# LED_Cube_with_Rs.net
KiCad netlist of a schematic drawn in EAGLE
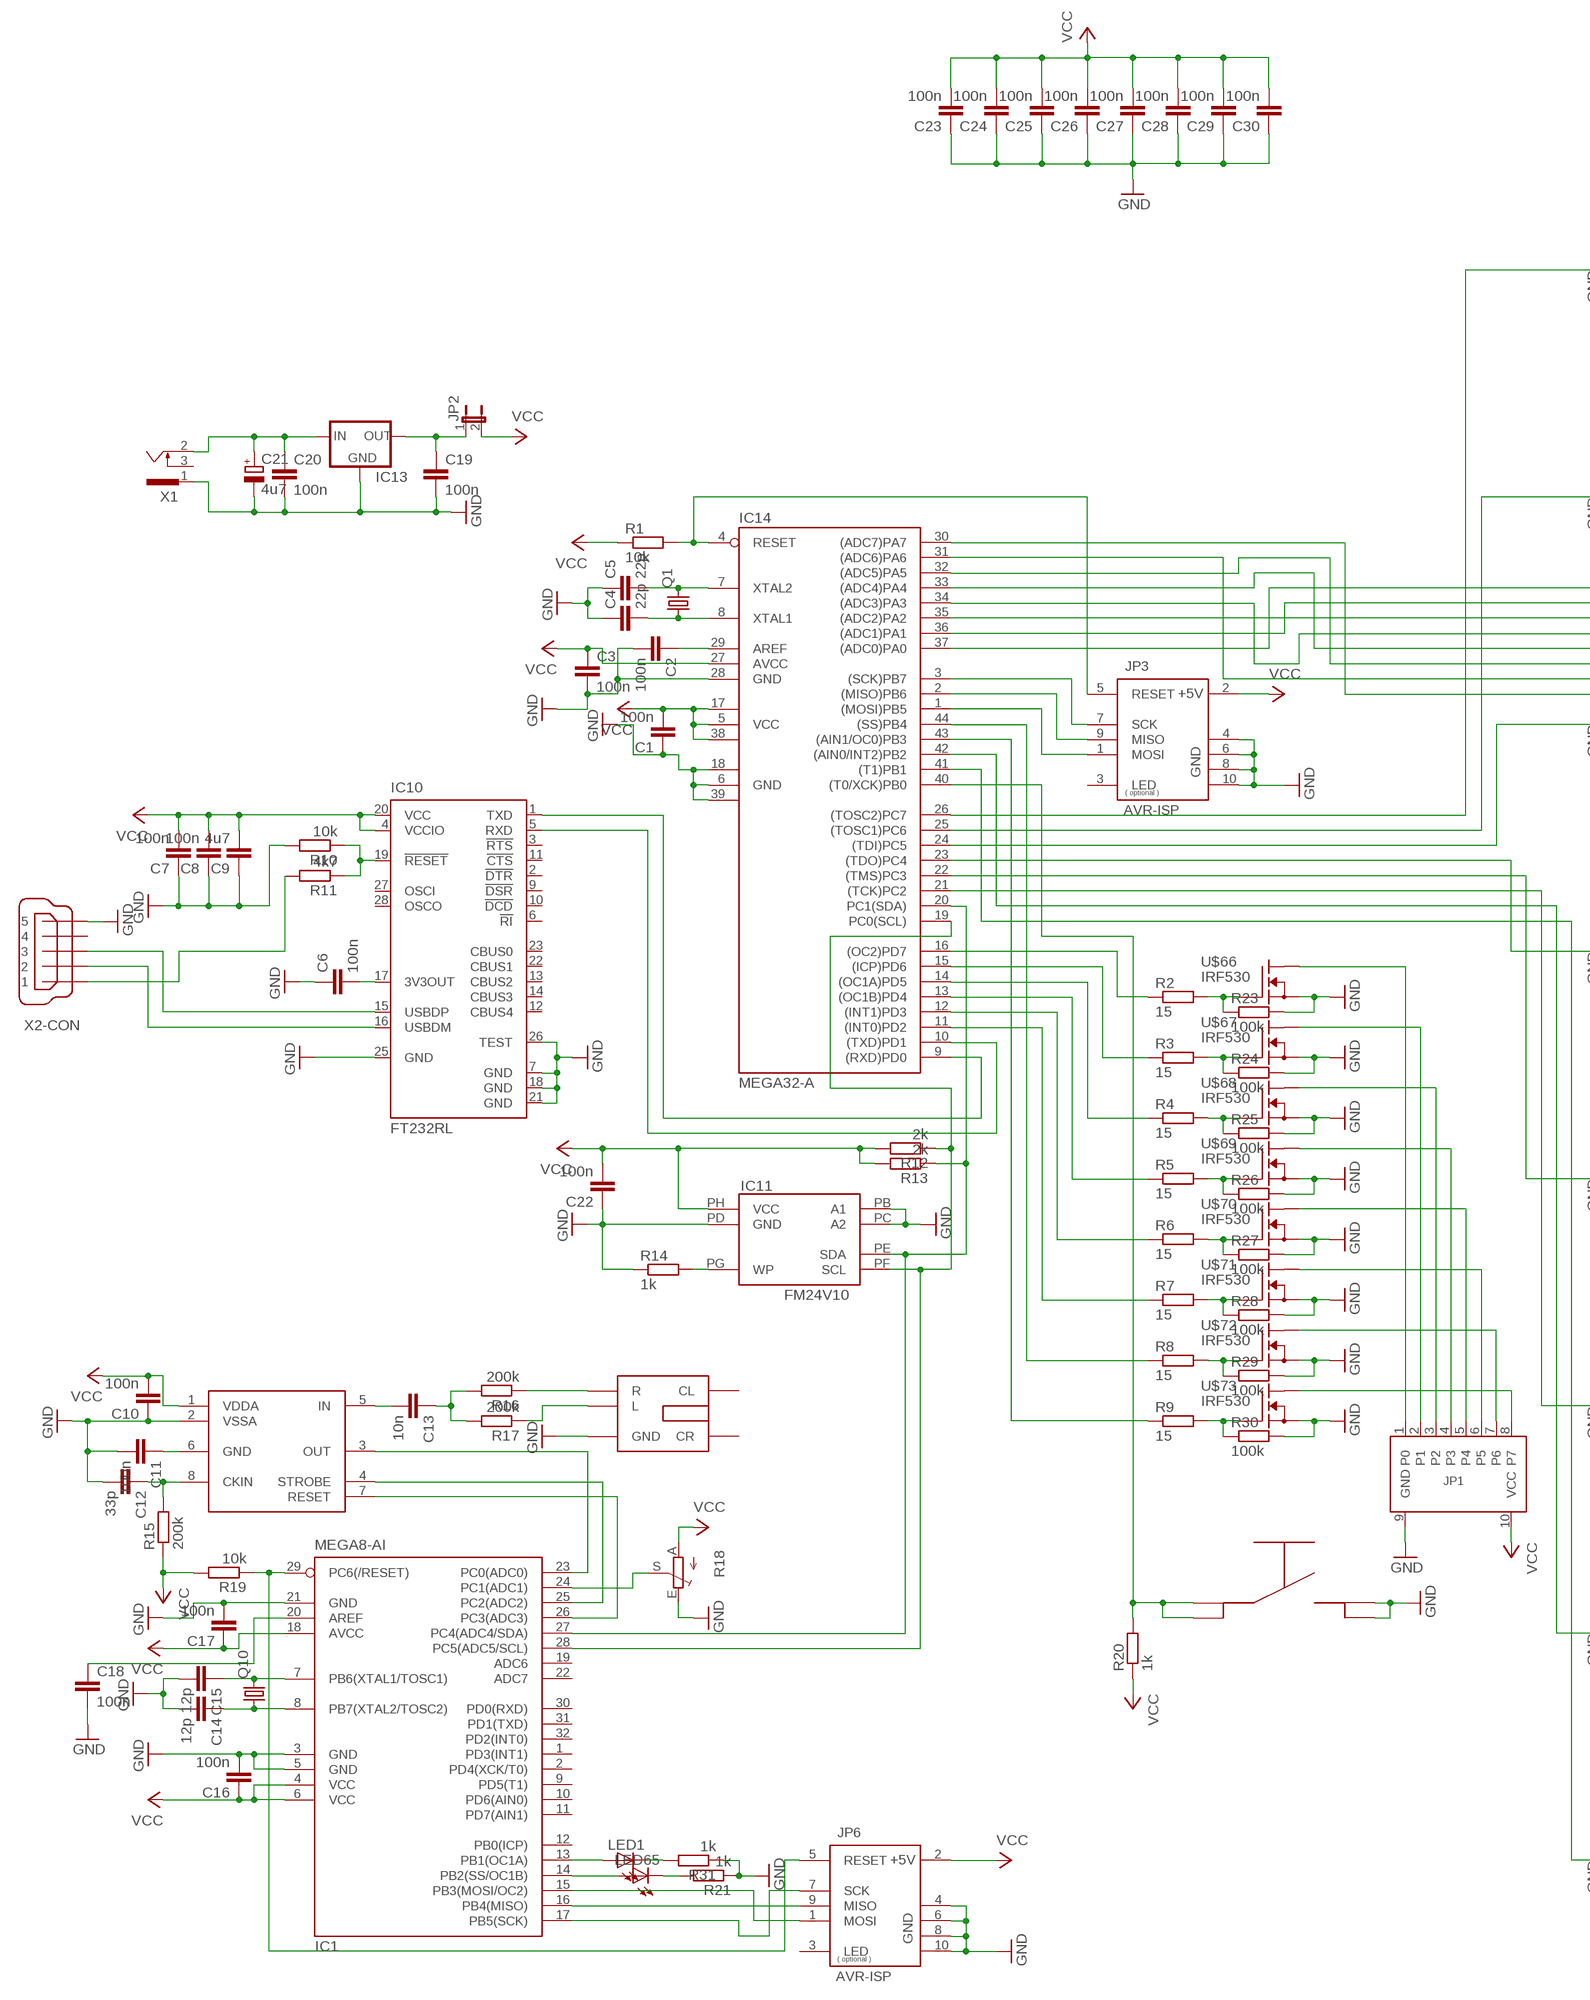
[diagram p0: schematic, sheet 1, part 1 of 2]
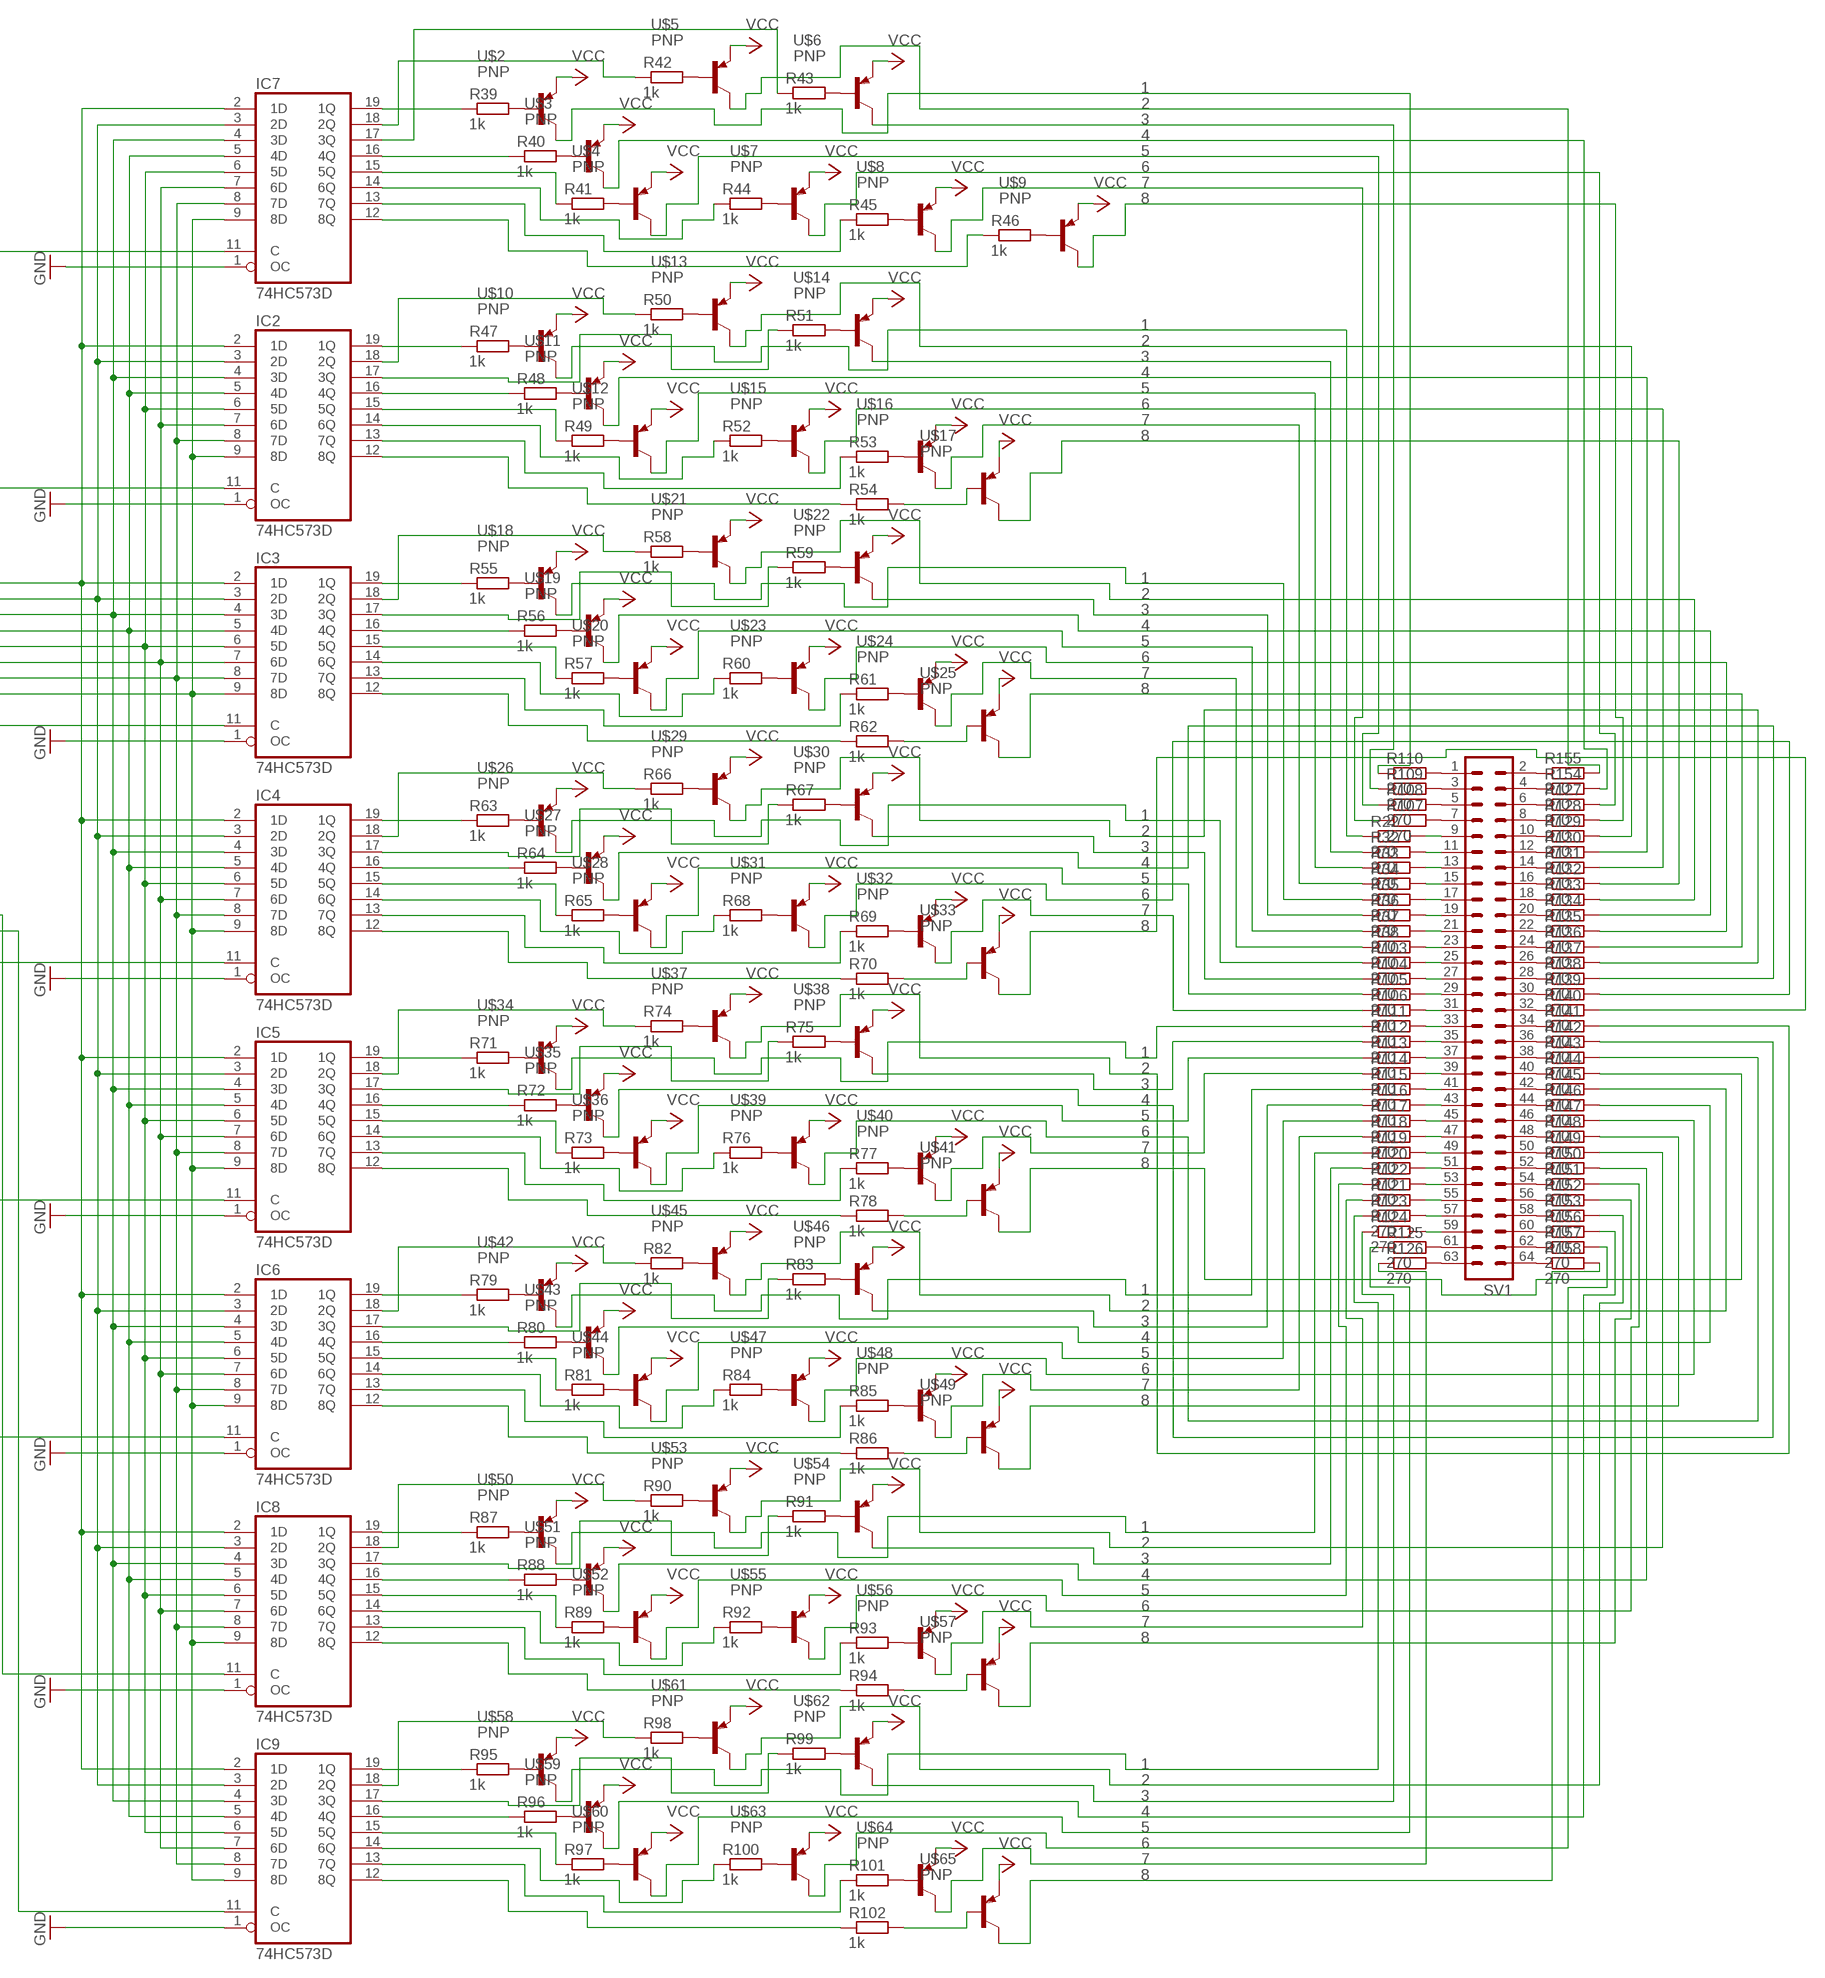
[diagram p1: schematic, sheet 1, part 2 of 2]

(export (version "E")
  (design (tool "Eeschema 10.0.6"))
  (components
    (comp (ref "C1")
      (value "100n")
      (footprint "eagle-import:C0603")
      (libsource (lib "eagle-import") (part "C-EUC0603"))
    )
    (comp (ref "C2")
      (value "100n")
      (footprint "eagle-import:C0603")
      (libsource (lib "eagle-import") (part "C-EUC0603"))
    )
    (comp (ref "C3")
      (value "100n")
      (footprint "eagle-import:C0603")
      (libsource (lib "eagle-import") (part "C-EUC0603"))
    )
    (comp (ref "C4")
      (value "22p")
      (footprint "eagle-import:C0603")
      (libsource (lib "eagle-import") (part "C-EUC0603"))
    )
    (comp (ref "C5")
      (value "22p")
      (footprint "eagle-import:C0603")
      (libsource (lib "eagle-import") (part "C-EUC0603"))
    )
    (comp (ref "C6")
      (value "100n")
      (footprint "eagle-import:C0603")
      (libsource (lib "eagle-import") (part "C-EUC0603"))
    )
    (comp (ref "C7")
      (value "100n")
      (footprint "eagle-import:C0603")
      (libsource (lib "eagle-import") (part "C-EUC0603"))
    )
    (comp (ref "C8")
      (value "100n")
      (footprint "eagle-import:C0603")
      (libsource (lib "eagle-import") (part "C-EUC0603"))
    )
    (comp (ref "C9")
      (value "4u7")
      (footprint "eagle-import:C0603")
      (libsource (lib "eagle-import") (part "C-EUC0603"))
    )
    (comp (ref "C10")
      (value "100n")
      (footprint "eagle-import:C0603")
      (libsource (lib "eagle-import") (part "C-EUC0603"))
    )
    (comp (ref "C11")
      (value "100n")
      (footprint "eagle-import:C0603")
      (libsource (lib "eagle-import") (part "C-EUC0603"))
    )
    (comp (ref "C12")
      (value "33p")
      (footprint "eagle-import:C0603")
      (libsource (lib "eagle-import") (part "C-EUC0603"))
    )
    (comp (ref "C13")
      (value "10n")
      (footprint "eagle-import:C0603")
      (libsource (lib "eagle-import") (part "C-EUC0603"))
    )
    (comp (ref "C14")
      (value "12p")
      (footprint "eagle-import:C0603")
      (libsource (lib "eagle-import") (part "C-EUC0603"))
    )
    (comp (ref "C15")
      (value "12p")
      (footprint "eagle-import:C0603")
      (libsource (lib "eagle-import") (part "C-EUC0603"))
    )
    (comp (ref "C16")
      (value "100n")
      (footprint "eagle-import:C0603")
      (libsource (lib "eagle-import") (part "C-EUC0603"))
    )
    (comp (ref "C17")
      (value "100n")
      (footprint "eagle-import:C0603")
      (libsource (lib "eagle-import") (part "C-EUC0603"))
    )
    (comp (ref "C18")
      (value "100n")
      (footprint "eagle-import:C0603")
      (libsource (lib "eagle-import") (part "C-EUC0603"))
    )
    (comp (ref "C19")
      (value "100n")
      (footprint "eagle-import:C0603")
      (libsource (lib "eagle-import") (part "C-EUC0603"))
    )
    (comp (ref "C20")
      (value "100n")
      (footprint "eagle-import:C0603")
      (libsource (lib "eagle-import") (part "C-EUC0603"))
    )
    (comp (ref "C21")
      (value "4u7")
      (footprint "eagle-import:TAP5-80")
      (libsource (lib "eagle-import") (part "CPOL-EUTAP5-80"))
    )
    (comp (ref "C22")
      (value "100n")
      (footprint "eagle-import:C0603")
      (libsource (lib "eagle-import") (part "C-EUC0603"))
    )
    (comp (ref "C23")
      (value "100n")
      (footprint "eagle-import:C0603")
      (libsource (lib "eagle-import") (part "C-EUC0603"))
    )
    (comp (ref "C24")
      (value "100n")
      (footprint "eagle-import:C0603")
      (libsource (lib "eagle-import") (part "C-EUC0603"))
    )
    (comp (ref "C25")
      (value "100n")
      (footprint "eagle-import:C0603")
      (libsource (lib "eagle-import") (part "C-EUC0603"))
    )
    (comp (ref "C26")
      (value "100n")
      (footprint "eagle-import:C0603")
      (libsource (lib "eagle-import") (part "C-EUC0603"))
    )
    (comp (ref "C27")
      (value "100n")
      (footprint "eagle-import:C0603")
      (libsource (lib "eagle-import") (part "C-EUC0603"))
    )
    (comp (ref "C28")
      (value "100n")
      (footprint "eagle-import:C0603")
      (libsource (lib "eagle-import") (part "C-EUC0603"))
    )
    (comp (ref "C29")
      (value "100n")
      (footprint "eagle-import:C0603")
      (libsource (lib "eagle-import") (part "C-EUC0603"))
    )
    (comp (ref "C30")
      (value "100n")
      (footprint "eagle-import:C0603")
      (libsource (lib "eagle-import") (part "C-EUC0603"))
    )
    (comp (ref "IC1")
      (value "MEGA8-AI")
      (footprint "eagle-import:TQFP32-08")
      (fields (field (name "MPN") "ATMEGA8-16AU"))
      (libsource (lib "eagle-import") (part "MEGA8-AI"))
    )
    (comp (ref "IC2")
      (value "74HC573D")
      (footprint "eagle-import:SO20W")
      (libsource (lib "eagle-import") (part "74573DHC"))
    )
    (comp (ref "IC3")
      (value "74HC573D")
      (footprint "eagle-import:SO20W")
      (libsource (lib "eagle-import") (part "74573DHC"))
    )
    (comp (ref "IC4")
      (value "74HC573D")
      (footprint "eagle-import:SO20W")
      (libsource (lib "eagle-import") (part "74573DHC"))
    )
    (comp (ref "IC5")
      (value "74HC573D")
      (footprint "eagle-import:SO20W")
      (libsource (lib "eagle-import") (part "74573DHC"))
    )
    (comp (ref "IC6")
      (value "74HC573D")
      (footprint "eagle-import:SO20W")
      (libsource (lib "eagle-import") (part "74573DHC"))
    )
    (comp (ref "IC7")
      (value "74HC573D")
      (footprint "eagle-import:SO20W")
      (libsource (lib "eagle-import") (part "74573DHC"))
    )
    (comp (ref "IC8")
      (value "74HC573D")
      (footprint "eagle-import:SO20W")
      (libsource (lib "eagle-import") (part "74573DHC"))
    )
    (comp (ref "IC9")
      (value "74HC573D")
      (footprint "eagle-import:SO20W")
      (libsource (lib "eagle-import") (part "74573DHC"))
    )
    (comp (ref "IC10")
      (value "FT232RL")
      (footprint "eagle-import:SSOP28")
      (libsource (lib "eagle-import") (part "FT232RL"))
    )
    (comp (ref "IC11")
      (value "FM24V10")
      (footprint "eagle-import:SOIC8")
      (libsource (lib "eagle-import") (part "FM24V10"))
    )
    (comp (ref "IC12")
      (value "MSGEQ7")
      (footprint "eagle-import:DIP8")
      (libsource (lib "eagle-import") (part "MSGEQ7"))
    )
    (comp (ref "IC13")
      (value "78XXS")
      (footprint "eagle-import:78XXS")
      (libsource (lib "eagle-import") (part "78XXS"))
    )
    (comp (ref "IC14")
      (value "MEGA32-A")
      (footprint "eagle-import:TQFP44")
      (fields (field (name "MPN") "ATMEGA32-16AU"))
      (libsource (lib "eagle-import") (part "MEGA32-A"))
    )
    (comp (ref "JP1")
      (value "PORT")
      (footprint "eagle-import:ML10")
      (libsource (lib "eagle-import") (part "PORT"))
    )
    (comp (ref "JP2")
      (value "JP1E")
      (footprint "eagle-import:JP1")
      (libsource (lib "eagle-import") (part "JP1E"))
    )
    (comp (ref "JP3")
      (value "AVR-ISP")
      (footprint "eagle-import:ML10")
      (libsource (lib "eagle-import") (part "AVR-ISP"))
    )
    (comp (ref "JP6")
      (value "AVR-ISP")
      (footprint "eagle-import:ML10")
      (libsource (lib "eagle-import") (part "AVR-ISP"))
    )
    (comp (ref "LED1")
      (value "LEDCHIPLED_0603")
      (footprint "eagle-import:CHIPLED_0603")
      (libsource (lib "eagle-import") (part "LEDCHIPLED_0603"))
    )
    (comp (ref "LED65")
      (value "LEDCHIPLED_0603")
      (footprint "eagle-import:CHIPLED_0603")
      (libsource (lib "eagle-import") (part "LEDCHIPLED_0603"))
    )
    (comp (ref "Q1")
      (value "CRYSTALHC49S")
      (footprint "eagle-import:HC49_S")
      (libsource (lib "eagle-import") (part "CRYSTALHC49S"))
    )
    (comp (ref "Q10")
      (value "CRYSTALHC49S")
      (footprint "eagle-import:HC49_S")
      (libsource (lib "eagle-import") (part "CRYSTALHC49S"))
    )
    (comp (ref "R1")
      (value "10k")
      (footprint "eagle-import:R0603")
      (libsource (lib "eagle-import") (part "R-EU_R0603"))
    )
    (comp (ref "R2")
      (value "15")
      (footprint "eagle-import:R0603")
      (libsource (lib "eagle-import") (part "R-EU_R0603"))
    )
    (comp (ref "R3")
      (value "15")
      (footprint "eagle-import:R0603")
      (libsource (lib "eagle-import") (part "R-EU_R0603"))
    )
    (comp (ref "R4")
      (value "15")
      (footprint "eagle-import:R0603")
      (libsource (lib "eagle-import") (part "R-EU_R0603"))
    )
    (comp (ref "R5")
      (value "15")
      (footprint "eagle-import:R0603")
      (libsource (lib "eagle-import") (part "R-EU_R0603"))
    )
    (comp (ref "R6")
      (value "15")
      (footprint "eagle-import:R0603")
      (libsource (lib "eagle-import") (part "R-EU_R0603"))
    )
    (comp (ref "R7")
      (value "15")
      (footprint "eagle-import:R0603")
      (libsource (lib "eagle-import") (part "R-EU_R0603"))
    )
    (comp (ref "R8")
      (value "15")
      (footprint "eagle-import:R0603")
      (libsource (lib "eagle-import") (part "R-EU_R0603"))
    )
    (comp (ref "R9")
      (value "15")
      (footprint "eagle-import:R0603")
      (libsource (lib "eagle-import") (part "R-EU_R0603"))
    )
    (comp (ref "R10")
      (value "10k")
      (footprint "eagle-import:R0603")
      (libsource (lib "eagle-import") (part "R-EU_R0603"))
    )
    (comp (ref "R11")
      (value "4k7")
      (footprint "eagle-import:R0603")
      (libsource (lib "eagle-import") (part "R-EU_R0603"))
    )
    (comp (ref "R12")
      (value "2k")
      (footprint "eagle-import:R0603")
      (libsource (lib "eagle-import") (part "R-EU_R0603"))
    )
    (comp (ref "R13")
      (value "2k")
      (footprint "eagle-import:R0603")
      (libsource (lib "eagle-import") (part "R-EU_R0603"))
    )
    (comp (ref "R14")
      (value "1k")
      (footprint "eagle-import:R0603")
      (libsource (lib "eagle-import") (part "R-EU_R0603"))
    )
    (comp (ref "R15")
      (value "200k")
      (footprint "eagle-import:R0603")
      (libsource (lib "eagle-import") (part "R-EU_R0603"))
    )
    (comp (ref "R16")
      (value "200k")
      (footprint "eagle-import:R0603")
      (libsource (lib "eagle-import") (part "R-EU_R0603"))
    )
    (comp (ref "R17")
      (value "200k")
      (footprint "eagle-import:R0603")
      (libsource (lib "eagle-import") (part "R-EU_R0603"))
    )
    (comp (ref "R18")
      (value "TRIM_EU-PT10S")
      (footprint "eagle-import:PT-10S")
      (libsource (lib "eagle-import") (part "TRIM_EU-PT10S"))
    )
    (comp (ref "R19")
      (value "10k")
      (footprint "eagle-import:R0603")
      (libsource (lib "eagle-import") (part "R-EU_R0603"))
    )
    (comp (ref "R20")
      (value "1k")
      (footprint "eagle-import:R0603")
      (libsource (lib "eagle-import") (part "R-EU_R0603"))
    )
    (comp (ref "R21")
      (value "1k")
      (footprint "eagle-import:R0603")
      (libsource (lib "eagle-import") (part "R-EU_R0603"))
    )
    (comp (ref "R22")
      (value "270")
      (footprint "eagle-import:R0603")
      (libsource (lib "eagle-import") (part "R-EU_R0603"))
    )
    (comp (ref "R23")
      (value "100k")
      (footprint "eagle-import:R0603")
      (libsource (lib "eagle-import") (part "R-EU_R0603"))
    )
    (comp (ref "R24")
      (value "100k")
      (footprint "eagle-import:R0603")
      (libsource (lib "eagle-import") (part "R-EU_R0603"))
    )
    (comp (ref "R25")
      (value "100k")
      (footprint "eagle-import:R0603")
      (libsource (lib "eagle-import") (part "R-EU_R0603"))
    )
    (comp (ref "R26")
      (value "100k")
      (footprint "eagle-import:R0603")
      (libsource (lib "eagle-import") (part "R-EU_R0603"))
    )
    (comp (ref "R27")
      (value "100k")
      (footprint "eagle-import:R0603")
      (libsource (lib "eagle-import") (part "R-EU_R0603"))
    )
    (comp (ref "R28")
      (value "100k")
      (footprint "eagle-import:R0603")
      (libsource (lib "eagle-import") (part "R-EU_R0603"))
    )
    (comp (ref "R29")
      (value "100k")
      (footprint "eagle-import:R0603")
      (libsource (lib "eagle-import") (part "R-EU_R0603"))
    )
    (comp (ref "R30")
      (value "100k")
      (footprint "eagle-import:R0603")
      (libsource (lib "eagle-import") (part "R-EU_R0603"))
    )
    (comp (ref "R31")
      (value "1k")
      (footprint "eagle-import:R0603")
      (libsource (lib "eagle-import") (part "R-EU_R0603"))
    )
    (comp (ref "R32")
      (value "270")
      (footprint "eagle-import:R0603")
      (libsource (lib "eagle-import") (part "R-EU_R0603"))
    )
    (comp (ref "R33")
      (value "270")
      (footprint "eagle-import:R0603")
      (libsource (lib "eagle-import") (part "R-EU_R0603"))
    )
    (comp (ref "R34")
      (value "270")
      (footprint "eagle-import:R0603")
      (libsource (lib "eagle-import") (part "R-EU_R0603"))
    )
    (comp (ref "R35")
      (value "270")
      (footprint "eagle-import:R0603")
      (libsource (lib "eagle-import") (part "R-EU_R0603"))
    )
    (comp (ref "R36")
      (value "270")
      (footprint "eagle-import:R0603")
      (libsource (lib "eagle-import") (part "R-EU_R0603"))
    )
    (comp (ref "R37")
      (value "270")
      (footprint "eagle-import:R0603")
      (libsource (lib "eagle-import") (part "R-EU_R0603"))
    )
    (comp (ref "R38")
      (value "270")
      (footprint "eagle-import:R0603")
      (libsource (lib "eagle-import") (part "R-EU_R0603"))
    )
    (comp (ref "R39")
      (value "1k")
      (footprint "eagle-import:R0603")
      (libsource (lib "eagle-import") (part "R-EU_R0603"))
    )
    (comp (ref "R40")
      (value "1k")
      (footprint "eagle-import:R0603")
      (libsource (lib "eagle-import") (part "R-EU_R0603"))
    )
    (comp (ref "R41")
      (value "1k")
      (footprint "eagle-import:R0603")
      (libsource (lib "eagle-import") (part "R-EU_R0603"))
    )
    (comp (ref "R42")
      (value "1k")
      (footprint "eagle-import:R0603")
      (libsource (lib "eagle-import") (part "R-EU_R0603"))
    )
    (comp (ref "R43")
      (value "1k")
      (footprint "eagle-import:R0603")
      (libsource (lib "eagle-import") (part "R-EU_R0603"))
    )
    (comp (ref "R44")
      (value "1k")
      (footprint "eagle-import:R0603")
      (libsource (lib "eagle-import") (part "R-EU_R0603"))
    )
    (comp (ref "R45")
      (value "1k")
      (footprint "eagle-import:R0603")
      (libsource (lib "eagle-import") (part "R-EU_R0603"))
    )
    (comp (ref "R46")
      (value "1k")
      (footprint "eagle-import:R0603")
      (libsource (lib "eagle-import") (part "R-EU_R0603"))
    )
    (comp (ref "R47")
      (value "1k")
      (footprint "eagle-import:R0603")
      (libsource (lib "eagle-import") (part "R-EU_R0603"))
    )
    (comp (ref "R48")
      (value "1k")
      (footprint "eagle-import:R0603")
      (libsource (lib "eagle-import") (part "R-EU_R0603"))
    )
    (comp (ref "R49")
      (value "1k")
      (footprint "eagle-import:R0603")
      (libsource (lib "eagle-import") (part "R-EU_R0603"))
    )
    (comp (ref "R50")
      (value "1k")
      (footprint "eagle-import:R0603")
      (libsource (lib "eagle-import") (part "R-EU_R0603"))
    )
    (comp (ref "R51")
      (value "1k")
      (footprint "eagle-import:R0603")
      (libsource (lib "eagle-import") (part "R-EU_R0603"))
    )
    (comp (ref "R52")
      (value "1k")
      (footprint "eagle-import:R0603")
      (libsource (lib "eagle-import") (part "R-EU_R0603"))
    )
    (comp (ref "R53")
      (value "1k")
      (footprint "eagle-import:R0603")
      (libsource (lib "eagle-import") (part "R-EU_R0603"))
    )
    (comp (ref "R54")
      (value "1k")
      (footprint "eagle-import:R0603")
      (libsource (lib "eagle-import") (part "R-EU_R0603"))
    )
    (comp (ref "R55")
      (value "1k")
      (footprint "eagle-import:R0603")
      (libsource (lib "eagle-import") (part "R-EU_R0603"))
    )
    (comp (ref "R56")
      (value "1k")
      (footprint "eagle-import:R0603")
      (libsource (lib "eagle-import") (part "R-EU_R0603"))
    )
    (comp (ref "R57")
      (value "1k")
      (footprint "eagle-import:R0603")
      (libsource (lib "eagle-import") (part "R-EU_R0603"))
    )
    (comp (ref "R58")
      (value "1k")
      (footprint "eagle-import:R0603")
      (libsource (lib "eagle-import") (part "R-EU_R0603"))
    )
    (comp (ref "R59")
      (value "1k")
      (footprint "eagle-import:R0603")
      (libsource (lib "eagle-import") (part "R-EU_R0603"))
    )
    (comp (ref "R60")
      (value "1k")
      (footprint "eagle-import:R0603")
      (libsource (lib "eagle-import") (part "R-EU_R0603"))
    )
    (comp (ref "R61")
      (value "1k")
      (footprint "eagle-import:R0603")
      (libsource (lib "eagle-import") (part "R-EU_R0603"))
    )
    (comp (ref "R62")
      (value "1k")
      (footprint "eagle-import:R0603")
      (libsource (lib "eagle-import") (part "R-EU_R0603"))
    )
    (comp (ref "R63")
      (value "1k")
      (footprint "eagle-import:R0603")
      (libsource (lib "eagle-import") (part "R-EU_R0603"))
    )
    (comp (ref "R64")
      (value "1k")
      (footprint "eagle-import:R0603")
      (libsource (lib "eagle-import") (part "R-EU_R0603"))
    )
    (comp (ref "R65")
      (value "1k")
      (footprint "eagle-import:R0603")
      (libsource (lib "eagle-import") (part "R-EU_R0603"))
    )
    (comp (ref "R66")
      (value "1k")
      (footprint "eagle-import:R0603")
      (libsource (lib "eagle-import") (part "R-EU_R0603"))
    )
    (comp (ref "R67")
      (value "1k")
      (footprint "eagle-import:R0603")
      (libsource (lib "eagle-import") (part "R-EU_R0603"))
    )
    (comp (ref "R68")
      (value "1k")
      (footprint "eagle-import:R0603")
      (libsource (lib "eagle-import") (part "R-EU_R0603"))
    )
    (comp (ref "R69")
      (value "1k")
      (footprint "eagle-import:R0603")
      (libsource (lib "eagle-import") (part "R-EU_R0603"))
    )
    (comp (ref "R70")
      (value "1k")
      (footprint "eagle-import:R0603")
      (libsource (lib "eagle-import") (part "R-EU_R0603"))
    )
    (comp (ref "R71")
      (value "1k")
      (footprint "eagle-import:R0603")
      (libsource (lib "eagle-import") (part "R-EU_R0603"))
    )
    (comp (ref "R72")
      (value "1k")
      (footprint "eagle-import:R0603")
      (libsource (lib "eagle-import") (part "R-EU_R0603"))
    )
    (comp (ref "R73")
      (value "1k")
      (footprint "eagle-import:R0603")
      (libsource (lib "eagle-import") (part "R-EU_R0603"))
    )
    (comp (ref "R74")
      (value "1k")
      (footprint "eagle-import:R0603")
      (libsource (lib "eagle-import") (part "R-EU_R0603"))
    )
    (comp (ref "R75")
      (value "1k")
      (footprint "eagle-import:R0603")
      (libsource (lib "eagle-import") (part "R-EU_R0603"))
    )
    (comp (ref "R76")
      (value "1k")
      (footprint "eagle-import:R0603")
      (libsource (lib "eagle-import") (part "R-EU_R0603"))
    )
    (comp (ref "R77")
      (value "1k")
      (footprint "eagle-import:R0603")
      (libsource (lib "eagle-import") (part "R-EU_R0603"))
    )
    (comp (ref "R78")
      (value "1k")
      (footprint "eagle-import:R0603")
      (libsource (lib "eagle-import") (part "R-EU_R0603"))
    )
    (comp (ref "R79")
      (value "1k")
      (footprint "eagle-import:R0603")
      (libsource (lib "eagle-import") (part "R-EU_R0603"))
    )
    (comp (ref "R80")
      (value "1k")
      (footprint "eagle-import:R0603")
      (libsource (lib "eagle-import") (part "R-EU_R0603"))
    )
    (comp (ref "R81")
      (value "1k")
      (footprint "eagle-import:R0603")
      (libsource (lib "eagle-import") (part "R-EU_R0603"))
    )
    (comp (ref "R82")
      (value "1k")
      (footprint "eagle-import:R0603")
      (libsource (lib "eagle-import") (part "R-EU_R0603"))
    )
    (comp (ref "R83")
      (value "1k")
      (footprint "eagle-import:R0603")
      (libsource (lib "eagle-import") (part "R-EU_R0603"))
    )
    (comp (ref "R84")
      (value "1k")
      (footprint "eagle-import:R0603")
      (libsource (lib "eagle-import") (part "R-EU_R0603"))
    )
    (comp (ref "R85")
      (value "1k")
      (footprint "eagle-import:R0603")
      (libsource (lib "eagle-import") (part "R-EU_R0603"))
    )
    (comp (ref "R86")
      (value "1k")
      (footprint "eagle-import:R0603")
      (libsource (lib "eagle-import") (part "R-EU_R0603"))
    )
    (comp (ref "R87")
      (value "1k")
      (footprint "eagle-import:R0603")
      (libsource (lib "eagle-import") (part "R-EU_R0603"))
    )
    (comp (ref "R88")
      (value "1k")
      (footprint "eagle-import:R0603")
      (libsource (lib "eagle-import") (part "R-EU_R0603"))
    )
    (comp (ref "R89")
      (value "1k")
      (footprint "eagle-import:R0603")
      (libsource (lib "eagle-import") (part "R-EU_R0603"))
    )
    (comp (ref "R90")
      (value "1k")
      (footprint "eagle-import:R0603")
      (libsource (lib "eagle-import") (part "R-EU_R0603"))
    )
    (comp (ref "R91")
      (value "1k")
      (footprint "eagle-import:R0603")
      (libsource (lib "eagle-import") (part "R-EU_R0603"))
    )
    (comp (ref "R92")
      (value "1k")
      (footprint "eagle-import:R0603")
      (libsource (lib "eagle-import") (part "R-EU_R0603"))
    )
    (comp (ref "R93")
      (value "1k")
      (footprint "eagle-import:R0603")
      (libsource (lib "eagle-import") (part "R-EU_R0603"))
    )
    (comp (ref "R94")
      (value "1k")
      (footprint "eagle-import:R0603")
      (libsource (lib "eagle-import") (part "R-EU_R0603"))
    )
    (comp (ref "R95")
      (value "1k")
      (footprint "eagle-import:R0603")
      (libsource (lib "eagle-import") (part "R-EU_R0603"))
    )
    (comp (ref "R96")
      (value "1k")
      (footprint "eagle-import:R0603")
      (libsource (lib "eagle-import") (part "R-EU_R0603"))
    )
    (comp (ref "R97")
      (value "1k")
      (footprint "eagle-import:R0603")
      (libsource (lib "eagle-import") (part "R-EU_R0603"))
    )
    (comp (ref "R98")
      (value "1k")
      (footprint "eagle-import:R0603")
      (libsource (lib "eagle-import") (part "R-EU_R0603"))
    )
    (comp (ref "R99")
      (value "1k")
      (footprint "eagle-import:R0603")
      (libsource (lib "eagle-import") (part "R-EU_R0603"))
    )
    (comp (ref "R100")
      (value "1k")
      (footprint "eagle-import:R0603")
      (libsource (lib "eagle-import") (part "R-EU_R0603"))
    )
    (comp (ref "R101")
      (value "1k")
      (footprint "eagle-import:R0603")
      (libsource (lib "eagle-import") (part "R-EU_R0603"))
    )
    (comp (ref "R102")
      (value "1k")
      (footprint "eagle-import:R0603")
      (libsource (lib "eagle-import") (part "R-EU_R0603"))
    )
    (comp (ref "R103")
      (value "270")
      (footprint "eagle-import:R0603")
      (libsource (lib "eagle-import") (part "R-EU_R0603"))
    )
    (comp (ref "R104")
      (value "270")
      (footprint "eagle-import:R0603")
      (libsource (lib "eagle-import") (part "R-EU_R0603"))
    )
    (comp (ref "R105")
      (value "270")
      (footprint "eagle-import:R0603")
      (libsource (lib "eagle-import") (part "R-EU_R0603"))
    )
    (comp (ref "R106")
      (value "270")
      (footprint "eagle-import:R0603")
      (libsource (lib "eagle-import") (part "R-EU_R0603"))
    )
    (comp (ref "R107")
      (value "270")
      (footprint "eagle-import:R0603")
      (libsource (lib "eagle-import") (part "R-EU_R0603"))
    )
    (comp (ref "R108")
      (value "270")
      (footprint "eagle-import:R0603")
      (libsource (lib "eagle-import") (part "R-EU_R0603"))
    )
    (comp (ref "R109")
      (value "270")
      (footprint "eagle-import:R0603")
      (libsource (lib "eagle-import") (part "R-EU_R0603"))
    )
    (comp (ref "R110")
      (value "270")
      (footprint "eagle-import:R0603")
      (libsource (lib "eagle-import") (part "R-EU_R0603"))
    )
    (comp (ref "R111")
      (value "270")
      (footprint "eagle-import:R0603")
      (libsource (lib "eagle-import") (part "R-EU_R0603"))
    )
    (comp (ref "R112")
      (value "270")
      (footprint "eagle-import:R0603")
      (libsource (lib "eagle-import") (part "R-EU_R0603"))
    )
    (comp (ref "R113")
      (value "270")
      (footprint "eagle-import:R0603")
      (libsource (lib "eagle-import") (part "R-EU_R0603"))
    )
    (comp (ref "R114")
      (value "270")
      (footprint "eagle-import:R0603")
      (libsource (lib "eagle-import") (part "R-EU_R0603"))
    )
    (comp (ref "R115")
      (value "270")
      (footprint "eagle-import:R0603")
      (libsource (lib "eagle-import") (part "R-EU_R0603"))
    )
    (comp (ref "R116")
      (value "270")
      (footprint "eagle-import:R0603")
      (libsource (lib "eagle-import") (part "R-EU_R0603"))
    )
    (comp (ref "R117")
      (value "270")
      (footprint "eagle-import:R0603")
      (libsource (lib "eagle-import") (part "R-EU_R0603"))
    )
    (comp (ref "R118")
      (value "270")
      (footprint "eagle-import:R0603")
      (libsource (lib "eagle-import") (part "R-EU_R0603"))
    )
    (comp (ref "R119")
      (value "270")
      (footprint "eagle-import:R0603")
      (libsource (lib "eagle-import") (part "R-EU_R0603"))
    )
    (comp (ref "R120")
      (value "270")
      (footprint "eagle-import:R0603")
      (libsource (lib "eagle-import") (part "R-EU_R0603"))
    )
    (comp (ref "R121")
      (value "270")
      (footprint "eagle-import:R0603")
      (libsource (lib "eagle-import") (part "R-EU_R0603"))
    )
    (comp (ref "R122")
      (value "270")
      (footprint "eagle-import:R0603")
      (libsource (lib "eagle-import") (part "R-EU_R0603"))
    )
    (comp (ref "R123")
      (value "270")
      (footprint "eagle-import:R0603")
      (libsource (lib "eagle-import") (part "R-EU_R0603"))
    )
    (comp (ref "R124")
      (value "270")
      (footprint "eagle-import:R0603")
      (libsource (lib "eagle-import") (part "R-EU_R0603"))
    )
    (comp (ref "R125")
      (value "270")
      (footprint "eagle-import:R0603")
      (libsource (lib "eagle-import") (part "R-EU_R0603"))
    )
    (comp (ref "R126")
      (value "270")
      (footprint "eagle-import:R0603")
      (libsource (lib "eagle-import") (part "R-EU_R0603"))
    )
    (comp (ref "R127")
      (value "270")
      (footprint "eagle-import:R0603")
      (libsource (lib "eagle-import") (part "R-EU_R0603"))
    )
    (comp (ref "R128")
      (value "270")
      (footprint "eagle-import:R0603")
      (libsource (lib "eagle-import") (part "R-EU_R0603"))
    )
    (comp (ref "R129")
      (value "270")
      (footprint "eagle-import:R0603")
      (libsource (lib "eagle-import") (part "R-EU_R0603"))
    )
    (comp (ref "R130")
      (value "270")
      (footprint "eagle-import:R0603")
      (libsource (lib "eagle-import") (part "R-EU_R0603"))
    )
    (comp (ref "R131")
      (value "270")
      (footprint "eagle-import:R0603")
      (libsource (lib "eagle-import") (part "R-EU_R0603"))
    )
    (comp (ref "R132")
      (value "270")
      (footprint "eagle-import:R0603")
      (libsource (lib "eagle-import") (part "R-EU_R0603"))
    )
    (comp (ref "R133")
      (value "270")
      (footprint "eagle-import:R0603")
      (libsource (lib "eagle-import") (part "R-EU_R0603"))
    )
    (comp (ref "R134")
      (value "270")
      (footprint "eagle-import:R0603")
      (libsource (lib "eagle-import") (part "R-EU_R0603"))
    )
    (comp (ref "R135")
      (value "270")
      (footprint "eagle-import:R0603")
      (libsource (lib "eagle-import") (part "R-EU_R0603"))
    )
    (comp (ref "R136")
      (value "270")
      (footprint "eagle-import:R0603")
      (libsource (lib "eagle-import") (part "R-EU_R0603"))
    )
    (comp (ref "R137")
      (value "270")
      (footprint "eagle-import:R0603")
      (libsource (lib "eagle-import") (part "R-EU_R0603"))
    )
    (comp (ref "R138")
      (value "270")
      (footprint "eagle-import:R0603")
      (libsource (lib "eagle-import") (part "R-EU_R0603"))
    )
    (comp (ref "R139")
      (value "270")
      (footprint "eagle-import:R0603")
      (libsource (lib "eagle-import") (part "R-EU_R0603"))
    )
    (comp (ref "R140")
      (value "270")
      (footprint "eagle-import:R0603")
      (libsource (lib "eagle-import") (part "R-EU_R0603"))
    )
    (comp (ref "R141")
      (value "270")
      (footprint "eagle-import:R0603")
      (libsource (lib "eagle-import") (part "R-EU_R0603"))
    )
    (comp (ref "R142")
      (value "270")
      (footprint "eagle-import:R0603")
      (libsource (lib "eagle-import") (part "R-EU_R0603"))
    )
    (comp (ref "R143")
      (value "270")
      (footprint "eagle-import:R0603")
      (libsource (lib "eagle-import") (part "R-EU_R0603"))
    )
    (comp (ref "R144")
      (value "270")
      (footprint "eagle-import:R0603")
      (libsource (lib "eagle-import") (part "R-EU_R0603"))
    )
    (comp (ref "R145")
      (value "270")
      (footprint "eagle-import:R0603")
      (libsource (lib "eagle-import") (part "R-EU_R0603"))
    )
    (comp (ref "R146")
      (value "270")
      (footprint "eagle-import:R0603")
      (libsource (lib "eagle-import") (part "R-EU_R0603"))
    )
    (comp (ref "R147")
      (value "270")
      (footprint "eagle-import:R0603")
      (libsource (lib "eagle-import") (part "R-EU_R0603"))
    )
    (comp (ref "R148")
      (value "270")
      (footprint "eagle-import:R0603")
      (libsource (lib "eagle-import") (part "R-EU_R0603"))
    )
    (comp (ref "R149")
      (value "270")
      (footprint "eagle-import:R0603")
      (libsource (lib "eagle-import") (part "R-EU_R0603"))
    )
    (comp (ref "R150")
      (value "270")
      (footprint "eagle-import:R0603")
      (libsource (lib "eagle-import") (part "R-EU_R0603"))
    )
    (comp (ref "R151")
      (value "270")
      (footprint "eagle-import:R0603")
      (libsource (lib "eagle-import") (part "R-EU_R0603"))
    )
    (comp (ref "R152")
      (value "270")
      (footprint "eagle-import:R0603")
      (libsource (lib "eagle-import") (part "R-EU_R0603"))
    )
    (comp (ref "R153")
      (value "270")
      (footprint "eagle-import:R0603")
      (libsource (lib "eagle-import") (part "R-EU_R0603"))
    )
    (comp (ref "R154")
      (value "270")
      (footprint "eagle-import:R0603")
      (libsource (lib "eagle-import") (part "R-EU_R0603"))
    )
    (comp (ref "R155")
      (value "270")
      (footprint "eagle-import:R0603")
      (libsource (lib "eagle-import") (part "R-EU_R0603"))
    )
    (comp (ref "R156")
      (value "270")
      (footprint "eagle-import:R0603")
      (libsource (lib "eagle-import") (part "R-EU_R0603"))
    )
    (comp (ref "R157")
      (value "270")
      (footprint "eagle-import:R0603")
      (libsource (lib "eagle-import") (part "R-EU_R0603"))
    )
    (comp (ref "R158")
      (value "270")
      (footprint "eagle-import:R0603")
      (libsource (lib "eagle-import") (part "R-EU_R0603"))
    )
    (comp (ref "SV1")
      (value "ML64")
      (footprint "eagle-import:ML64")
      (libsource (lib "eagle-import") (part "ML64"))
    )
    (comp (ref "U$1")
      (value "KLINKENBUCHSE")
      (footprint "eagle-import:KLINKEPRINT")
      (libsource (lib "eagle-import") (part "KLINKENBUCHSE"))
    )
    (comp (ref "U$2")
      (value "PNP")
      (footprint "eagle-import:SOT323")
      (libsource (lib "eagle-import") (part "PNP"))
    )
    (comp (ref "U$3")
      (value "PNP")
      (footprint "eagle-import:SOT323")
      (libsource (lib "eagle-import") (part "PNP"))
    )
    (comp (ref "U$4")
      (value "PNP")
      (footprint "eagle-import:SOT323")
      (libsource (lib "eagle-import") (part "PNP"))
    )
    (comp (ref "U$5")
      (value "PNP")
      (footprint "eagle-import:SOT323")
      (libsource (lib "eagle-import") (part "PNP"))
    )
    (comp (ref "U$6")
      (value "PNP")
      (footprint "eagle-import:SOT323")
      (libsource (lib "eagle-import") (part "PNP"))
    )
    (comp (ref "U$7")
      (value "PNP")
      (footprint "eagle-import:SOT323")
      (libsource (lib "eagle-import") (part "PNP"))
    )
    (comp (ref "U$8")
      (value "PNP")
      (footprint "eagle-import:SOT323")
      (libsource (lib "eagle-import") (part "PNP"))
    )
    (comp (ref "U$9")
      (value "PNP")
      (footprint "eagle-import:SOT323")
      (libsource (lib "eagle-import") (part "PNP"))
    )
    (comp (ref "U$10")
      (value "PNP")
      (footprint "eagle-import:SOT323")
      (libsource (lib "eagle-import") (part "PNP"))
    )
    (comp (ref "U$11")
      (value "PNP")
      (footprint "eagle-import:SOT323")
      (libsource (lib "eagle-import") (part "PNP"))
    )
    (comp (ref "U$12")
      (value "PNP")
      (footprint "eagle-import:SOT323")
      (libsource (lib "eagle-import") (part "PNP"))
    )
    (comp (ref "U$13")
      (value "PNP")
      (footprint "eagle-import:SOT323")
      (libsource (lib "eagle-import") (part "PNP"))
    )
    (comp (ref "U$14")
      (value "PNP")
      (footprint "eagle-import:SOT323")
      (libsource (lib "eagle-import") (part "PNP"))
    )
    (comp (ref "U$15")
      (value "PNP")
      (footprint "eagle-import:SOT323")
      (libsource (lib "eagle-import") (part "PNP"))
    )
    (comp (ref "U$16")
      (value "PNP")
      (footprint "eagle-import:SOT323")
      (libsource (lib "eagle-import") (part "PNP"))
    )
    (comp (ref "U$17")
      (value "PNP")
      (footprint "eagle-import:SOT323")
      (libsource (lib "eagle-import") (part "PNP"))
    )
    (comp (ref "U$18")
      (value "PNP")
      (footprint "eagle-import:SOT323")
      (libsource (lib "eagle-import") (part "PNP"))
    )
    (comp (ref "U$19")
      (value "PNP")
      (footprint "eagle-import:SOT323")
      (libsource (lib "eagle-import") (part "PNP"))
    )
    (comp (ref "U$20")
      (value "PNP")
      (footprint "eagle-import:SOT323")
      (libsource (lib "eagle-import") (part "PNP"))
    )
    (comp (ref "U$21")
      (value "PNP")
      (footprint "eagle-import:SOT323")
      (libsource (lib "eagle-import") (part "PNP"))
    )
    (comp (ref "U$22")
      (value "PNP")
      (footprint "eagle-import:SOT323")
      (libsource (lib "eagle-import") (part "PNP"))
    )
    (comp (ref "U$23")
      (value "PNP")
      (footprint "eagle-import:SOT323")
      (libsource (lib "eagle-import") (part "PNP"))
    )
    (comp (ref "U$24")
      (value "PNP")
      (footprint "eagle-import:SOT323")
      (libsource (lib "eagle-import") (part "PNP"))
    )
    (comp (ref "U$25")
      (value "PNP")
      (footprint "eagle-import:SOT323")
      (libsource (lib "eagle-import") (part "PNP"))
    )
    (comp (ref "U$26")
      (value "PNP")
      (footprint "eagle-import:SOT323")
      (libsource (lib "eagle-import") (part "PNP"))
    )
    (comp (ref "U$27")
      (value "PNP")
      (footprint "eagle-import:SOT323")
      (libsource (lib "eagle-import") (part "PNP"))
    )
    (comp (ref "U$28")
      (value "PNP")
      (footprint "eagle-import:SOT323")
      (libsource (lib "eagle-import") (part "PNP"))
    )
    (comp (ref "U$29")
      (value "PNP")
      (footprint "eagle-import:SOT323")
      (libsource (lib "eagle-import") (part "PNP"))
    )
    (comp (ref "U$30")
      (value "PNP")
      (footprint "eagle-import:SOT323")
      (libsource (lib "eagle-import") (part "PNP"))
    )
    (comp (ref "U$31")
      (value "PNP")
      (footprint "eagle-import:SOT323")
      (libsource (lib "eagle-import") (part "PNP"))
    )
    (comp (ref "U$32")
      (value "PNP")
      (footprint "eagle-import:SOT323")
      (libsource (lib "eagle-import") (part "PNP"))
    )
    (comp (ref "U$33")
      (value "PNP")
      (footprint "eagle-import:SOT323")
      (libsource (lib "eagle-import") (part "PNP"))
    )
    (comp (ref "U$34")
      (value "PNP")
      (footprint "eagle-import:SOT323")
      (libsource (lib "eagle-import") (part "PNP"))
    )
    (comp (ref "U$35")
      (value "PNP")
      (footprint "eagle-import:SOT323")
      (libsource (lib "eagle-import") (part "PNP"))
    )
    (comp (ref "U$36")
      (value "PNP")
      (footprint "eagle-import:SOT323")
      (libsource (lib "eagle-import") (part "PNP"))
    )
    (comp (ref "U$37")
      (value "PNP")
      (footprint "eagle-import:SOT323")
      (libsource (lib "eagle-import") (part "PNP"))
    )
    (comp (ref "U$38")
      (value "PNP")
      (footprint "eagle-import:SOT323")
      (libsource (lib "eagle-import") (part "PNP"))
    )
    (comp (ref "U$39")
      (value "PNP")
      (footprint "eagle-import:SOT323")
      (libsource (lib "eagle-import") (part "PNP"))
    )
    (comp (ref "U$40")
      (value "PNP")
      (footprint "eagle-import:SOT323")
      (libsource (lib "eagle-import") (part "PNP"))
    )
    (comp (ref "U$41")
      (value "PNP")
      (footprint "eagle-import:SOT323")
      (libsource (lib "eagle-import") (part "PNP"))
    )
    (comp (ref "U$42")
      (value "PNP")
      (footprint "eagle-import:SOT323")
      (libsource (lib "eagle-import") (part "PNP"))
    )
    (comp (ref "U$43")
      (value "PNP")
      (footprint "eagle-import:SOT323")
      (libsource (lib "eagle-import") (part "PNP"))
    )
    (comp (ref "U$44")
      (value "PNP")
      (footprint "eagle-import:SOT323")
      (libsource (lib "eagle-import") (part "PNP"))
    )
    (comp (ref "U$45")
      (value "PNP")
      (footprint "eagle-import:SOT323")
      (libsource (lib "eagle-import") (part "PNP"))
    )
    (comp (ref "U$46")
      (value "PNP")
      (footprint "eagle-import:SOT323")
      (libsource (lib "eagle-import") (part "PNP"))
    )
    (comp (ref "U$47")
      (value "PNP")
      (footprint "eagle-import:SOT323")
      (libsource (lib "eagle-import") (part "PNP"))
    )
    (comp (ref "U$48")
      (value "PNP")
      (footprint "eagle-import:SOT323")
      (libsource (lib "eagle-import") (part "PNP"))
    )
    (comp (ref "U$49")
      (value "PNP")
      (footprint "eagle-import:SOT323")
      (libsource (lib "eagle-import") (part "PNP"))
    )
    (comp (ref "U$50")
      (value "PNP")
      (footprint "eagle-import:SOT323")
      (libsource (lib "eagle-import") (part "PNP"))
    )
    (comp (ref "U$51")
      (value "PNP")
      (footprint "eagle-import:SOT323")
      (libsource (lib "eagle-import") (part "PNP"))
    )
    (comp (ref "U$52")
      (value "PNP")
      (footprint "eagle-import:SOT323")
      (libsource (lib "eagle-import") (part "PNP"))
    )
    (comp (ref "U$53")
      (value "PNP")
      (footprint "eagle-import:SOT323")
      (libsource (lib "eagle-import") (part "PNP"))
    )
    (comp (ref "U$54")
      (value "PNP")
      (footprint "eagle-import:SOT323")
      (libsource (lib "eagle-import") (part "PNP"))
    )
    (comp (ref "U$55")
      (value "PNP")
      (footprint "eagle-import:SOT323")
      (libsource (lib "eagle-import") (part "PNP"))
    )
    (comp (ref "U$56")
      (value "PNP")
      (footprint "eagle-import:SOT323")
      (libsource (lib "eagle-import") (part "PNP"))
    )
    (comp (ref "U$57")
      (value "PNP")
      (footprint "eagle-import:SOT323")
      (libsource (lib "eagle-import") (part "PNP"))
    )
    (comp (ref "U$58")
      (value "PNP")
      (footprint "eagle-import:SOT323")
      (libsource (lib "eagle-import") (part "PNP"))
    )
    (comp (ref "U$59")
      (value "PNP")
      (footprint "eagle-import:SOT323")
      (libsource (lib "eagle-import") (part "PNP"))
    )
    (comp (ref "U$60")
      (value "PNP")
      (footprint "eagle-import:SOT323")
      (libsource (lib "eagle-import") (part "PNP"))
    )
    (comp (ref "U$61")
      (value "PNP")
      (footprint "eagle-import:SOT323")
      (libsource (lib "eagle-import") (part "PNP"))
    )
    (comp (ref "U$62")
      (value "PNP")
      (footprint "eagle-import:SOT323")
      (libsource (lib "eagle-import") (part "PNP"))
    )
    (comp (ref "U$63")
      (value "PNP")
      (footprint "eagle-import:SOT323")
      (libsource (lib "eagle-import") (part "PNP"))
    )
    (comp (ref "U$64")
      (value "PNP")
      (footprint "eagle-import:SOT323")
      (libsource (lib "eagle-import") (part "PNP"))
    )
    (comp (ref "U$65")
      (value "PNP")
      (footprint "eagle-import:SOT323")
      (libsource (lib "eagle-import") (part "PNP"))
    )
    (comp (ref "U$66")
      (value "IRF530")
      (footprint "eagle-import:TO220-3V")
      (libsource (lib "eagle-import") (part "IRF530"))
    )
    (comp (ref "U$67")
      (value "IRF530")
      (footprint "eagle-import:TO220-3V")
      (libsource (lib "eagle-import") (part "IRF530"))
    )
    (comp (ref "U$68")
      (value "IRF530")
      (footprint "eagle-import:TO220-3V")
      (libsource (lib "eagle-import") (part "IRF530"))
    )
    (comp (ref "U$69")
      (value "IRF530")
      (footprint "eagle-import:TO220-3V")
      (libsource (lib "eagle-import") (part "IRF530"))
    )
    (comp (ref "U$70")
      (value "IRF530")
      (footprint "eagle-import:TO220-3V")
      (libsource (lib "eagle-import") (part "IRF530"))
    )
    (comp (ref "U$71")
      (value "IRF530")
      (footprint "eagle-import:TO220-3V")
      (libsource (lib "eagle-import") (part "IRF530"))
    )
    (comp (ref "U$72")
      (value "IRF530")
      (footprint "eagle-import:TO220-3V")
      (libsource (lib "eagle-import") (part "IRF530"))
    )
    (comp (ref "U$73")
      (value "IRF530")
      (footprint "eagle-import:TO220-3V")
      (libsource (lib "eagle-import") (part "IRF530"))
    )
    (comp (ref "U$74")
      (value "TASTER")
      (footprint "eagle-import:SMDTASTER")
      (libsource (lib "eagle-import") (part "TASTER"))
    )
    (comp (ref "X1")
      (value "733980-62")
      (footprint "eagle-import:733980-62")
      (libsource (lib "eagle-import") (part "73398?0-62"))
    )
    (comp (ref "X2")
      (value "USB-B-MINI-SMD")
      (footprint "eagle-import:USB-B-MINI-SMD")
      (libsource (lib "eagle-import") (part "USB-B-MINI-SMD"))
    )
  )
  (nets
    (net (code "1") (name "GND") (class "Default")
      (node (ref "C1") (pin "1") (pinfunction "1_1") (pintype "passive"))
      (node (ref "C10") (pin "1") (pinfunction "1_1") (pintype "passive"))
      (node (ref "C11") (pin "2") (pinfunction "2_2") (pintype "passive"))
      (node (ref "C12") (pin "2") (pinfunction "2_2") (pintype "passive"))
      (node (ref "C14") (pin "2") (pinfunction "2_2") (pintype "passive"))
      (node (ref "C15") (pin "2") (pinfunction "2_2") (pintype "passive"))
      (node (ref "C16") (pin "2") (pinfunction "2_2") (pintype "passive"))
      (node (ref "C17") (pin "2") (pinfunction "2_2") (pintype "passive"))
      (node (ref "C18") (pin "2") (pinfunction "2_2") (pintype "passive"))
      (node (ref "C19") (pin "2") (pinfunction "2_2") (pintype "passive"))
      (node (ref "C2") (pin "2") (pinfunction "2_2") (pintype "passive"))
      (node (ref "C20") (pin "2") (pinfunction "2_2") (pintype "passive"))
      (node (ref "C21") (pin "-") (pinfunction "-_-") (pintype "passive"))
      (node (ref "C22") (pin "1") (pinfunction "1_1") (pintype "passive"))
      (node (ref "C23") (pin "1") (pinfunction "1_1") (pintype "passive"))
      (node (ref "C24") (pin "1") (pinfunction "1_1") (pintype "passive"))
      (node (ref "C25") (pin "1") (pinfunction "1_1") (pintype "passive"))
      (node (ref "C26") (pin "1") (pinfunction "1_1") (pintype "passive"))
      (node (ref "C27") (pin "1") (pinfunction "1_1") (pintype "passive"))
      (node (ref "C28") (pin "1") (pinfunction "1_1") (pintype "passive"))
      (node (ref "C29") (pin "1") (pinfunction "1_1") (pintype "passive"))
      (node (ref "C3") (pin "2") (pinfunction "2_2") (pintype "passive"))
      (node (ref "C30") (pin "1") (pinfunction "1_1") (pintype "passive"))
      (node (ref "C4") (pin "1") (pinfunction "1_1") (pintype "passive"))
      (node (ref "C5") (pin "1") (pinfunction "1_1") (pintype "passive"))
      (node (ref "C6") (pin "1") (pinfunction "1_1") (pintype "passive"))
      (node (ref "C7") (pin "1") (pinfunction "1_1") (pintype "passive"))
      (node (ref "C8") (pin "1") (pinfunction "1_1") (pintype "passive"))
      (node (ref "C9") (pin "1") (pinfunction "1_1") (pintype "passive"))
      (node (ref "IC1") (pin "21") (pinfunction "GND_21") (pintype "power_in"))
      (node (ref "IC1") (pin "3") (pinfunction "GND_3") (pintype "power_in"))
      (node (ref "IC1") (pin "5") (pinfunction "GND_5") (pintype "power_in"))
      (node (ref "IC10") (pin "18") (pinfunction "GND_18") (pintype "power_in"))
      (node (ref "IC10") (pin "21") (pinfunction "GND_21") (pintype "power_in"))
      (node (ref "IC10") (pin "25") (pinfunction "GND_25") (pintype "power_in"))
      (node (ref "IC10") (pin "26") (pinfunction "TEST_26") (pintype "input"))
      (node (ref "IC10") (pin "7") (pinfunction "GND_7") (pintype "power_in"))
      (node (ref "IC11") (pin "PB") (pinfunction "A1_PB") (pintype "input"))
      (node (ref "IC11") (pin "PC") (pinfunction "A2_PC") (pintype "input"))
      (node (ref "IC11") (pin "PD") (pinfunction "GND_PD") (pintype "power_in"))
      (node (ref "IC12") (pin "2") (pinfunction "VSSA_2") (pintype "power_in"))
      (node (ref "IC13") (pin "GND") (pinfunction "GND_GND") (pintype "input"))
      (node (ref "IC14") (pin "18") (pinfunction "GND1_18") (pintype "power_in"))
      (node (ref "IC14") (pin "28") (pinfunction "GND_28") (pintype "power_in"))
      (node (ref "IC14") (pin "39") (pinfunction "GND2_39") (pintype "power_in"))
      (node (ref "IC14") (pin "6") (pinfunction "GND_6") (pintype "power_in"))
      (node (ref "IC2") (pin "1") (pinfunction "OC_1") (pintype "input"))
      (node (ref "IC3") (pin "1") (pinfunction "OC_1") (pintype "input"))
      (node (ref "IC4") (pin "1") (pinfunction "OC_1") (pintype "input"))
      (node (ref "IC5") (pin "1") (pinfunction "OC_1") (pintype "input"))
      (node (ref "IC6") (pin "1") (pinfunction "OC_1") (pintype "input"))
      (node (ref "IC7") (pin "1") (pinfunction "OC_1") (pintype "input"))
      (node (ref "IC8") (pin "1") (pinfunction "OC_1") (pintype "input"))
      (node (ref "IC9") (pin "1") (pinfunction "OC_1") (pintype "input"))
      (node (ref "JP1") (pin "9") (pinfunction "GND_9") (pintype "power_in"))
      (node (ref "JP3") (pin "10") (pinfunction "GND_10") (pintype "power_in"))
      (node (ref "JP3") (pin "4") (pinfunction "GND_4") (pintype "power_in"))
      (node (ref "JP3") (pin "6") (pinfunction "GND_6") (pintype "power_in"))
      (node (ref "JP3") (pin "8") (pinfunction "GND_8") (pintype "power_in"))
      (node (ref "JP6") (pin "10") (pinfunction "GND_10") (pintype "power_in"))
      (node (ref "JP6") (pin "4") (pinfunction "GND_4") (pintype "power_in"))
      (node (ref "JP6") (pin "6") (pinfunction "GND_6") (pintype "power_in"))
      (node (ref "JP6") (pin "8") (pinfunction "GND_8") (pintype "power_in"))
      (node (ref "R10") (pin "2") (pinfunction "2_2") (pintype "passive"))
      (node (ref "R14") (pin "1") (pinfunction "1_1") (pintype "passive"))
      (node (ref "R18") (pin "E") (pinfunction "E_E") (pintype "passive"))
      (node (ref "R21") (pin "1") (pinfunction "1_1") (pintype "passive"))
      (node (ref "R23") (pin "2") (pinfunction "2_2") (pintype "passive"))
      (node (ref "R24") (pin "2") (pinfunction "2_2") (pintype "passive"))
      (node (ref "R25") (pin "2") (pinfunction "2_2") (pintype "passive"))
      (node (ref "R26") (pin "2") (pinfunction "2_2") (pintype "passive"))
      (node (ref "R27") (pin "2") (pinfunction "2_2") (pintype "passive"))
      (node (ref "R28") (pin "2") (pinfunction "2_2") (pintype "passive"))
      (node (ref "R29") (pin "2") (pinfunction "2_2") (pintype "passive"))
      (node (ref "R30") (pin "2") (pinfunction "2_2") (pintype "passive"))
      (node (ref "R31") (pin "1") (pinfunction "1_1") (pintype "passive"))
      (node (ref "U$1") (pin "GND") (pinfunction "GND_GND") (pintype "bidirectional"))
      (node (ref "U$66") (pin "3") (pinfunction "S_3") (pintype "passive"))
      (node (ref "U$67") (pin "3") (pinfunction "S_3") (pintype "passive"))
      (node (ref "U$68") (pin "3") (pinfunction "S_3") (pintype "passive"))
      (node (ref "U$69") (pin "3") (pinfunction "S_3") (pintype "passive"))
      (node (ref "U$70") (pin "3") (pinfunction "S_3") (pintype "passive"))
      (node (ref "U$71") (pin "3") (pinfunction "S_3") (pintype "passive"))
      (node (ref "U$72") (pin "3") (pinfunction "S_3") (pintype "passive"))
      (node (ref "U$73") (pin "3") (pinfunction "S_3") (pintype "passive"))
      (node (ref "U$74") (pin "B") (pinfunction "B_B") (pintype "bidirectional"))
      (node (ref "U$74") (pin "B2") (pinfunction "B2_B2") (pintype "bidirectional"))
      (node (ref "X1") (pin "1") (pinfunction "1_1") (pintype "passive"))
      (node (ref "X2") (pin "5") (pinfunction "5_5") (pintype "input"))
    )
    (net (code "2") (name "Net-(C13-Pad1)") (class "Default")
      (node (ref "C13") (pin "1") (pinfunction "1_1") (pintype "passive"))
      (node (ref "R16") (pin "2") (pinfunction "2_2") (pintype "passive"))
      (node (ref "R17") (pin "2") (pinfunction "2_2") (pintype "passive"))
    )
    (net (code "3") (name "Net-(C19-Pad1)") (class "Default")
      (node (ref "C19") (pin "1") (pinfunction "1_1") (pintype "passive"))
      (node (ref "IC13") (pin "OUT") (pinfunction "OUT_OUT") (pintype "passive"))
      (node (ref "JP2") (pin "1") (pinfunction "1_1") (pintype "passive"))
    )
    (net (code "4") (name "Net-(C20-Pad1)") (class "Default")
      (node (ref "C20") (pin "1") (pinfunction "1_1") (pintype "passive"))
      (node (ref "C21") (pin "+") (pinfunction "+_+") (pintype "passive"))
      (node (ref "IC13") (pin "IN") (pinfunction "IN_IN") (pintype "input"))
      (node (ref "X1") (pin "2") (pinfunction "2_2") (pintype "passive"))
    )
    (net (code "5") (name "Net-(IC1-AREF)") (class "Default")
      (node (ref "C18") (pin "1") (pinfunction "1_1") (pintype "passive"))
      (node (ref "IC1") (pin "20") (pinfunction "AREF_20") (pintype "passive"))
    )
    (net (code "6") (name "Net-(IC1-PB1(OC1A))") (class "Default")
      (node (ref "IC1") (pin "13") (pinfunction "PB1(OC1A)_13") (pintype "bidirectional"))
      (node (ref "LED1") (pin "A") (pinfunction "A_A") (pintype "passive"))
    )
    (net (code "7") (name "Net-(IC1-PB2(SS{slash}OC1B))") (class "Default")
      (node (ref "IC1") (pin "14") (pinfunction "PB2(SS/OC1B)_14") (pintype "bidirectional"))
      (node (ref "LED65") (pin "A") (pinfunction "A_A") (pintype "passive"))
    )
    (net (code "8") (name "Net-(IC1-PB3(MOSI{slash}OC2))") (class "Default")
      (node (ref "IC1") (pin "15") (pinfunction "PB3(MOSI/OC2)_15") (pintype "bidirectional"))
      (node (ref "JP6") (pin "1") (pinfunction "MOSI_1") (pintype "bidirectional"))
    )
    (net (code "9") (name "Net-(IC1-PB4(MISO))") (class "Default")
      (node (ref "IC1") (pin "16") (pinfunction "PB4(MISO)_16") (pintype "bidirectional"))
      (node (ref "JP6") (pin "9") (pinfunction "MISO_9") (pintype "bidirectional"))
    )
    (net (code "10") (name "Net-(IC1-PB5(SCK))") (class "Default")
      (node (ref "IC1") (pin "17") (pinfunction "PB5(SCK)_17") (pintype "bidirectional"))
      (node (ref "JP6") (pin "7") (pinfunction "SCK_7") (pintype "input"))
    )
    (net (code "11") (name "Net-(IC1-PB6(XTAL1{slash}TOSC1))") (class "Default")
      (node (ref "C15") (pin "1") (pinfunction "1_1") (pintype "passive"))
      (node (ref "IC1") (pin "7") (pinfunction "PB6(XTAL1/TOSC1)_7") (pintype "bidirectional"))
      (node (ref "Q10") (pin "2") (pinfunction "2_2") (pintype "passive"))
    )
    (net (code "12") (name "Net-(IC1-PB7(XTAL2{slash}TOSC2))") (class "Default")
      (node (ref "C14") (pin "1") (pinfunction "1_1") (pintype "passive"))
      (node (ref "IC1") (pin "8") (pinfunction "PB7(XTAL2/TOSC2)_8") (pintype "bidirectional"))
      (node (ref "Q10") (pin "1") (pinfunction "1_1") (pintype "passive"))
    )
    (net (code "13") (name "Net-(IC1-PC0(ADC0))") (class "Default")
      (node (ref "IC1") (pin "23") (pinfunction "PC0(ADC0)_23") (pintype "bidirectional"))
      (node (ref "IC12") (pin "3") (pinfunction "OUT_3") (pintype "output"))
    )
    (net (code "14") (name "Net-(IC1-PC1(ADC1))") (class "Default")
      (node (ref "IC1") (pin "24") (pinfunction "PC1(ADC1)_24") (pintype "bidirectional"))
      (node (ref "R18") (pin "S") (pinfunction "S_S") (pintype "passive"))
    )
    (net (code "15") (name "Net-(IC1-PC2(ADC2))") (class "Default")
      (node (ref "IC1") (pin "25") (pinfunction "PC2(ADC2)_25") (pintype "bidirectional"))
      (node (ref "IC12") (pin "4") (pinfunction "STROBE_4") (pintype "input"))
    )
    (net (code "16") (name "Net-(IC1-PC3(ADC3))") (class "Default")
      (node (ref "IC1") (pin "26") (pinfunction "PC3(ADC3)_26") (pintype "bidirectional"))
      (node (ref "IC12") (pin "7") (pinfunction "RESET_7") (pintype "input"))
    )
    (net (code "17") (name "Net-(IC1-PC4(ADC4{slash}SDA))") (class "Default")
      (node (ref "IC1") (pin "27") (pinfunction "PC4(ADC4/SDA)_27") (pintype "bidirectional"))
      (node (ref "IC11") (pin "PE") (pinfunction "SDA_PE") (pintype "bidirectional"))
      (node (ref "IC14") (pin "20") (pinfunction "PC1(SDA)_20") (pintype "bidirectional"))
      (node (ref "R13") (pin "1") (pinfunction "1_1") (pintype "passive"))
    )
    (net (code "18") (name "Net-(IC1-PC5(ADC5{slash}SCL))") (class "Default")
      (node (ref "IC1") (pin "28") (pinfunction "PC5(ADC5/SCL)_28") (pintype "bidirectional"))
      (node (ref "IC11") (pin "PF") (pinfunction "SCL_PF") (pintype "bidirectional"))
      (node (ref "IC14") (pin "19") (pinfunction "PC0(SCL)_19") (pintype "bidirectional"))
      (node (ref "R12") (pin "1") (pinfunction "1_1") (pintype "passive"))
    )
    (net (code "19") (name "Net-(IC1-PC6({slash}RESET))") (class "Default")
      (node (ref "IC1") (pin "29") (pinfunction "PC6(/RESET)_29") (pintype "bidirectional"))
      (node (ref "JP6") (pin "5") (pinfunction "RESET_5") (pintype "input"))
      (node (ref "R19") (pin "1") (pinfunction "1_1") (pintype "passive"))
    )
    (net (code "20") (name "Net-(IC2A-1Q)") (class "Default")
      (node (ref "IC2") (pin "19") (pinfunction "1Q_19") (pintype "tri_state"))
      (node (ref "R47") (pin "1") (pinfunction "1_1") (pintype "passive"))
    )
    (net (code "21") (name "Net-(IC2A-2Q)") (class "Default")
      (node (ref "IC2") (pin "18") (pinfunction "2Q_18") (pintype "tri_state"))
      (node (ref "R50") (pin "1") (pinfunction "1_1") (pintype "passive"))
    )
    (net (code "22") (name "Net-(IC2A-3Q)") (class "Default")
      (node (ref "IC2") (pin "17") (pinfunction "3Q_17") (pintype "tri_state"))
      (node (ref "R51") (pin "1") (pinfunction "1_1") (pintype "passive"))
    )
    (net (code "23") (name "Net-(IC2A-4Q)") (class "Default")
      (node (ref "IC2") (pin "16") (pinfunction "4Q_16") (pintype "tri_state"))
      (node (ref "R48") (pin "1") (pinfunction "1_1") (pintype "passive"))
    )
    (net (code "24") (name "Net-(IC2A-5Q)") (class "Default")
      (node (ref "IC2") (pin "15") (pinfunction "5Q_15") (pintype "tri_state"))
      (node (ref "R49") (pin "1") (pinfunction "1_1") (pintype "passive"))
    )
    (net (code "25") (name "Net-(IC2A-6Q)") (class "Default")
      (node (ref "IC2") (pin "14") (pinfunction "6Q_14") (pintype "tri_state"))
      (node (ref "R52") (pin "1") (pinfunction "1_1") (pintype "passive"))
    )
    (net (code "26") (name "Net-(IC2A-7Q)") (class "Default")
      (node (ref "IC2") (pin "13") (pinfunction "7Q_13") (pintype "tri_state"))
      (node (ref "R53") (pin "1") (pinfunction "1_1") (pintype "passive"))
    )
    (net (code "27") (name "Net-(IC2A-8Q)") (class "Default")
      (node (ref "IC2") (pin "12") (pinfunction "8Q_12") (pintype "tri_state"))
      (node (ref "R54") (pin "1") (pinfunction "1_1") (pintype "passive"))
    )
    (net (code "28") (name "Net-(IC3A-1Q)") (class "Default")
      (node (ref "IC3") (pin "19") (pinfunction "1Q_19") (pintype "tri_state"))
      (node (ref "R55") (pin "1") (pinfunction "1_1") (pintype "passive"))
    )
    (net (code "29") (name "Net-(IC3A-2Q)") (class "Default")
      (node (ref "IC3") (pin "18") (pinfunction "2Q_18") (pintype "tri_state"))
      (node (ref "R58") (pin "1") (pinfunction "1_1") (pintype "passive"))
    )
    (net (code "30") (name "Net-(IC3A-3Q)") (class "Default")
      (node (ref "IC3") (pin "17") (pinfunction "3Q_17") (pintype "tri_state"))
      (node (ref "R59") (pin "1") (pinfunction "1_1") (pintype "passive"))
    )
    (net (code "31") (name "Net-(IC3A-4Q)") (class "Default")
      (node (ref "IC3") (pin "16") (pinfunction "4Q_16") (pintype "tri_state"))
      (node (ref "R56") (pin "1") (pinfunction "1_1") (pintype "passive"))
    )
    (net (code "32") (name "Net-(IC3A-5Q)") (class "Default")
      (node (ref "IC3") (pin "15") (pinfunction "5Q_15") (pintype "tri_state"))
      (node (ref "R57") (pin "1") (pinfunction "1_1") (pintype "passive"))
    )
    (net (code "33") (name "Net-(IC3A-6Q)") (class "Default")
      (node (ref "IC3") (pin "14") (pinfunction "6Q_14") (pintype "tri_state"))
      (node (ref "R60") (pin "1") (pinfunction "1_1") (pintype "passive"))
    )
    (net (code "34") (name "Net-(IC3A-7Q)") (class "Default")
      (node (ref "IC3") (pin "13") (pinfunction "7Q_13") (pintype "tri_state"))
      (node (ref "R61") (pin "1") (pinfunction "1_1") (pintype "passive"))
    )
    (net (code "35") (name "Net-(IC3A-8Q)") (class "Default")
      (node (ref "IC3") (pin "12") (pinfunction "8Q_12") (pintype "tri_state"))
      (node (ref "R62") (pin "1") (pinfunction "1_1") (pintype "passive"))
    )
    (net (code "36") (name "Net-(IC4A-1Q)") (class "Default")
      (node (ref "IC4") (pin "19") (pinfunction "1Q_19") (pintype "tri_state"))
      (node (ref "R63") (pin "1") (pinfunction "1_1") (pintype "passive"))
    )
    (net (code "37") (name "Net-(IC4A-2Q)") (class "Default")
      (node (ref "IC4") (pin "18") (pinfunction "2Q_18") (pintype "tri_state"))
      (node (ref "R66") (pin "1") (pinfunction "1_1") (pintype "passive"))
    )
    (net (code "38") (name "Net-(IC4A-3Q)") (class "Default")
      (node (ref "IC4") (pin "17") (pinfunction "3Q_17") (pintype "tri_state"))
      (node (ref "R67") (pin "1") (pinfunction "1_1") (pintype "passive"))
    )
    (net (code "39") (name "Net-(IC4A-4Q)") (class "Default")
      (node (ref "IC4") (pin "16") (pinfunction "4Q_16") (pintype "tri_state"))
      (node (ref "R64") (pin "1") (pinfunction "1_1") (pintype "passive"))
    )
    (net (code "40") (name "Net-(IC4A-5Q)") (class "Default")
      (node (ref "IC4") (pin "15") (pinfunction "5Q_15") (pintype "tri_state"))
      (node (ref "R65") (pin "1") (pinfunction "1_1") (pintype "passive"))
    )
    (net (code "41") (name "Net-(IC4A-6Q)") (class "Default")
      (node (ref "IC4") (pin "14") (pinfunction "6Q_14") (pintype "tri_state"))
      (node (ref "R68") (pin "1") (pinfunction "1_1") (pintype "passive"))
    )
    (net (code "42") (name "Net-(IC4A-7Q)") (class "Default")
      (node (ref "IC4") (pin "13") (pinfunction "7Q_13") (pintype "tri_state"))
      (node (ref "R69") (pin "1") (pinfunction "1_1") (pintype "passive"))
    )
    (net (code "43") (name "Net-(IC4A-8Q)") (class "Default")
      (node (ref "IC4") (pin "12") (pinfunction "8Q_12") (pintype "tri_state"))
      (node (ref "R70") (pin "1") (pinfunction "1_1") (pintype "passive"))
    )
    (net (code "44") (name "Net-(IC5A-1Q)") (class "Default")
      (node (ref "IC5") (pin "19") (pinfunction "1Q_19") (pintype "tri_state"))
      (node (ref "R71") (pin "1") (pinfunction "1_1") (pintype "passive"))
    )
    (net (code "45") (name "Net-(IC5A-2Q)") (class "Default")
      (node (ref "IC5") (pin "18") (pinfunction "2Q_18") (pintype "tri_state"))
      (node (ref "R74") (pin "1") (pinfunction "1_1") (pintype "passive"))
    )
    (net (code "46") (name "Net-(IC5A-3Q)") (class "Default")
      (node (ref "IC5") (pin "17") (pinfunction "3Q_17") (pintype "tri_state"))
      (node (ref "R75") (pin "1") (pinfunction "1_1") (pintype "passive"))
    )
    (net (code "47") (name "Net-(IC5A-4Q)") (class "Default")
      (node (ref "IC5") (pin "16") (pinfunction "4Q_16") (pintype "tri_state"))
      (node (ref "R72") (pin "1") (pinfunction "1_1") (pintype "passive"))
    )
    (net (code "48") (name "Net-(IC5A-5Q)") (class "Default")
      (node (ref "IC5") (pin "15") (pinfunction "5Q_15") (pintype "tri_state"))
      (node (ref "R73") (pin "1") (pinfunction "1_1") (pintype "passive"))
    )
    (net (code "49") (name "Net-(IC5A-6Q)") (class "Default")
      (node (ref "IC5") (pin "14") (pinfunction "6Q_14") (pintype "tri_state"))
      (node (ref "R76") (pin "1") (pinfunction "1_1") (pintype "passive"))
    )
    (net (code "50") (name "Net-(IC5A-7Q)") (class "Default")
      (node (ref "IC5") (pin "13") (pinfunction "7Q_13") (pintype "tri_state"))
      (node (ref "R77") (pin "1") (pinfunction "1_1") (pintype "passive"))
    )
    (net (code "51") (name "Net-(IC5A-8Q)") (class "Default")
      (node (ref "IC5") (pin "12") (pinfunction "8Q_12") (pintype "tri_state"))
      (node (ref "R78") (pin "1") (pinfunction "1_1") (pintype "passive"))
    )
    (net (code "52") (name "Net-(IC6A-1Q)") (class "Default")
      (node (ref "IC6") (pin "19") (pinfunction "1Q_19") (pintype "tri_state"))
      (node (ref "R79") (pin "1") (pinfunction "1_1") (pintype "passive"))
    )
    (net (code "53") (name "Net-(IC6A-2Q)") (class "Default")
      (node (ref "IC6") (pin "18") (pinfunction "2Q_18") (pintype "tri_state"))
      (node (ref "R82") (pin "1") (pinfunction "1_1") (pintype "passive"))
    )
    (net (code "54") (name "Net-(IC6A-3Q)") (class "Default")
      (node (ref "IC6") (pin "17") (pinfunction "3Q_17") (pintype "tri_state"))
      (node (ref "R83") (pin "1") (pinfunction "1_1") (pintype "passive"))
    )
    (net (code "55") (name "Net-(IC6A-4Q)") (class "Default")
      (node (ref "IC6") (pin "16") (pinfunction "4Q_16") (pintype "tri_state"))
      (node (ref "R80") (pin "1") (pinfunction "1_1") (pintype "passive"))
    )
    (net (code "56") (name "Net-(IC6A-5Q)") (class "Default")
      (node (ref "IC6") (pin "15") (pinfunction "5Q_15") (pintype "tri_state"))
      (node (ref "R81") (pin "1") (pinfunction "1_1") (pintype "passive"))
    )
    (net (code "57") (name "Net-(IC6A-6Q)") (class "Default")
      (node (ref "IC6") (pin "14") (pinfunction "6Q_14") (pintype "tri_state"))
      (node (ref "R84") (pin "1") (pinfunction "1_1") (pintype "passive"))
    )
    (net (code "58") (name "Net-(IC6A-7Q)") (class "Default")
      (node (ref "IC6") (pin "13") (pinfunction "7Q_13") (pintype "tri_state"))
      (node (ref "R85") (pin "1") (pinfunction "1_1") (pintype "passive"))
    )
    (net (code "59") (name "Net-(IC6A-8Q)") (class "Default")
      (node (ref "IC6") (pin "12") (pinfunction "8Q_12") (pintype "tri_state"))
      (node (ref "R86") (pin "1") (pinfunction "1_1") (pintype "passive"))
    )
    (net (code "60") (name "Net-(IC7A-1Q)") (class "Default")
      (node (ref "IC7") (pin "19") (pinfunction "1Q_19") (pintype "tri_state"))
      (node (ref "R39") (pin "1") (pinfunction "1_1") (pintype "passive"))
    )
    (net (code "61") (name "Net-(IC7A-2Q)") (class "Default")
      (node (ref "IC7") (pin "18") (pinfunction "2Q_18") (pintype "tri_state"))
      (node (ref "R42") (pin "1") (pinfunction "1_1") (pintype "passive"))
    )
    (net (code "62") (name "Net-(IC7A-3Q)") (class "Default")
      (node (ref "IC7") (pin "17") (pinfunction "3Q_17") (pintype "tri_state"))
      (node (ref "R43") (pin "1") (pinfunction "1_1") (pintype "passive"))
    )
    (net (code "63") (name "Net-(IC7A-4Q)") (class "Default")
      (node (ref "IC7") (pin "16") (pinfunction "4Q_16") (pintype "tri_state"))
      (node (ref "R40") (pin "1") (pinfunction "1_1") (pintype "passive"))
    )
    (net (code "64") (name "Net-(IC7A-5Q)") (class "Default")
      (node (ref "IC7") (pin "15") (pinfunction "5Q_15") (pintype "tri_state"))
      (node (ref "R41") (pin "1") (pinfunction "1_1") (pintype "passive"))
    )
    (net (code "65") (name "Net-(IC7A-6Q)") (class "Default")
      (node (ref "IC7") (pin "14") (pinfunction "6Q_14") (pintype "tri_state"))
      (node (ref "R44") (pin "1") (pinfunction "1_1") (pintype "passive"))
    )
    (net (code "66") (name "Net-(IC7A-7Q)") (class "Default")
      (node (ref "IC7") (pin "13") (pinfunction "7Q_13") (pintype "tri_state"))
      (node (ref "R45") (pin "1") (pinfunction "1_1") (pintype "passive"))
    )
    (net (code "67") (name "Net-(IC7A-8Q)") (class "Default")
      (node (ref "IC7") (pin "12") (pinfunction "8Q_12") (pintype "tri_state"))
      (node (ref "R46") (pin "1") (pinfunction "1_1") (pintype "passive"))
    )
    (net (code "68") (name "Net-(IC8A-1Q)") (class "Default")
      (node (ref "IC8") (pin "19") (pinfunction "1Q_19") (pintype "tri_state"))
      (node (ref "R87") (pin "1") (pinfunction "1_1") (pintype "passive"))
    )
    (net (code "69") (name "Net-(IC8A-2Q)") (class "Default")
      (node (ref "IC8") (pin "18") (pinfunction "2Q_18") (pintype "tri_state"))
      (node (ref "R90") (pin "1") (pinfunction "1_1") (pintype "passive"))
    )
    (net (code "70") (name "Net-(IC8A-3Q)") (class "Default")
      (node (ref "IC8") (pin "17") (pinfunction "3Q_17") (pintype "tri_state"))
      (node (ref "R91") (pin "1") (pinfunction "1_1") (pintype "passive"))
    )
    (net (code "71") (name "Net-(IC8A-4Q)") (class "Default")
      (node (ref "IC8") (pin "16") (pinfunction "4Q_16") (pintype "tri_state"))
      (node (ref "R88") (pin "1") (pinfunction "1_1") (pintype "passive"))
    )
    (net (code "72") (name "Net-(IC8A-5Q)") (class "Default")
      (node (ref "IC8") (pin "15") (pinfunction "5Q_15") (pintype "tri_state"))
      (node (ref "R89") (pin "1") (pinfunction "1_1") (pintype "passive"))
    )
    (net (code "73") (name "Net-(IC8A-6Q)") (class "Default")
      (node (ref "IC8") (pin "14") (pinfunction "6Q_14") (pintype "tri_state"))
      (node (ref "R92") (pin "1") (pinfunction "1_1") (pintype "passive"))
    )
    (net (code "74") (name "Net-(IC8A-7Q)") (class "Default")
      (node (ref "IC8") (pin "13") (pinfunction "7Q_13") (pintype "tri_state"))
      (node (ref "R93") (pin "1") (pinfunction "1_1") (pintype "passive"))
    )
    (net (code "75") (name "Net-(IC8A-8Q)") (class "Default")
      (node (ref "IC8") (pin "12") (pinfunction "8Q_12") (pintype "tri_state"))
      (node (ref "R94") (pin "1") (pinfunction "1_1") (pintype "passive"))
    )
    (net (code "76") (name "Net-(IC9A-1Q)") (class "Default")
      (node (ref "IC9") (pin "19") (pinfunction "1Q_19") (pintype "tri_state"))
      (node (ref "R95") (pin "1") (pinfunction "1_1") (pintype "passive"))
    )
    (net (code "77") (name "Net-(IC9A-2Q)") (class "Default")
      (node (ref "IC9") (pin "18") (pinfunction "2Q_18") (pintype "tri_state"))
      (node (ref "R98") (pin "1") (pinfunction "1_1") (pintype "passive"))
    )
    (net (code "78") (name "Net-(IC9A-3Q)") (class "Default")
      (node (ref "IC9") (pin "17") (pinfunction "3Q_17") (pintype "tri_state"))
      (node (ref "R99") (pin "1") (pinfunction "1_1") (pintype "passive"))
    )
    (net (code "79") (name "Net-(IC9A-4Q)") (class "Default")
      (node (ref "IC9") (pin "16") (pinfunction "4Q_16") (pintype "tri_state"))
      (node (ref "R96") (pin "1") (pinfunction "1_1") (pintype "passive"))
    )
    (net (code "80") (name "Net-(IC9A-5Q)") (class "Default")
      (node (ref "IC9") (pin "15") (pinfunction "5Q_15") (pintype "tri_state"))
      (node (ref "R97") (pin "1") (pinfunction "1_1") (pintype "passive"))
    )
    (net (code "81") (name "Net-(IC9A-6Q)") (class "Default")
      (node (ref "IC9") (pin "14") (pinfunction "6Q_14") (pintype "tri_state"))
      (node (ref "R100") (pin "1") (pinfunction "1_1") (pintype "passive"))
    )
    (net (code "82") (name "Net-(IC9A-7Q)") (class "Default")
      (node (ref "IC9") (pin "13") (pinfunction "7Q_13") (pintype "tri_state"))
      (node (ref "R101") (pin "1") (pinfunction "1_1") (pintype "passive"))
    )
    (net (code "83") (name "Net-(IC9A-8Q)") (class "Default")
      (node (ref "IC9") (pin "12") (pinfunction "8Q_12") (pintype "tri_state"))
      (node (ref "R102") (pin "1") (pinfunction "1_1") (pintype "passive"))
    )
    (net (code "84") (name "Net-(IC10-3V3OUT)") (class "Default")
      (node (ref "C6") (pin "2") (pinfunction "2_2") (pintype "passive"))
      (node (ref "IC10") (pin "17") (pinfunction "3V3OUT_17") (pintype "output"))
    )
    (net (code "85") (name "Net-(IC10-RXD)") (class "Default")
      (node (ref "IC10") (pin "5") (pinfunction "RXD_5") (pintype "input"))
      (node (ref "IC14") (pin "10") (pinfunction "(TXD)PD1_10") (pintype "bidirectional"))
    )
    (net (code "86") (name "Net-(IC10-TXD)") (class "Default")
      (node (ref "IC10") (pin "1") (pinfunction "TXD_1") (pintype "output"))
      (node (ref "IC14") (pin "9") (pinfunction "(RXD)PD0_9") (pintype "bidirectional"))
    )
    (net (code "87") (name "Net-(IC10-USBDM)") (class "Default")
      (node (ref "IC10") (pin "16") (pinfunction "USBDM_16") (pintype "bidirectional"))
      (node (ref "X2") (pin "2") (pinfunction "2_2") (pintype "input"))
    )
    (net (code "88") (name "Net-(IC10-USBDP)") (class "Default")
      (node (ref "IC10") (pin "15") (pinfunction "USBDP_15") (pintype "bidirectional"))
      (node (ref "X2") (pin "3") (pinfunction "3_3") (pintype "input"))
    )
    (net (code "89") (name "Net-(IC10-~{RESET})") (class "Default")
      (node (ref "IC10") (pin "19") (pinfunction "~{RESET}_19") (pintype "input"))
      (node (ref "R10") (pin "1") (pinfunction "1_1") (pintype "passive"))
      (node (ref "R11") (pin "1") (pinfunction "1_1") (pintype "passive"))
    )
    (net (code "90") (name "Net-(IC11-WP)") (class "Default")
      (node (ref "IC11") (pin "PG") (pinfunction "WP_PG") (pintype "input"))
      (node (ref "R14") (pin "2") (pinfunction "2_2") (pintype "passive"))
    )
    (net (code "91") (name "Net-(IC12-CKIN)") (class "Default")
      (node (ref "C12") (pin "1") (pinfunction "1_1") (pintype "passive"))
      (node (ref "IC12") (pin "8") (pinfunction "CKIN_8") (pintype "input"))
      (node (ref "R15") (pin "2") (pinfunction "2_2") (pintype "passive"))
    )
    (net (code "92") (name "Net-(IC12-GND)") (class "Default")
      (node (ref "C11") (pin "1") (pinfunction "1_1") (pintype "passive"))
      (node (ref "IC12") (pin "6") (pinfunction "GND_6") (pintype "power_in"))
    )
    (net (code "93") (name "Net-(IC12-IN)") (class "Default")
      (node (ref "C13") (pin "2") (pinfunction "2_2") (pintype "passive"))
      (node (ref "IC12") (pin "5") (pinfunction "IN_5") (pintype "input"))
    )
    (net (code "94") (name "Net-(IC14-(ADC0)PA0)") (class "Default")
      (node (ref "IC14") (pin "37") (pinfunction "(ADC0)PA0_37") (pintype "bidirectional"))
      (node (ref "IC2") (pin "2") (pinfunction "1D_2") (pintype "input"))
      (node (ref "IC3") (pin "2") (pinfunction "1D_2") (pintype "input"))
      (node (ref "IC4") (pin "2") (pinfunction "1D_2") (pintype "input"))
      (node (ref "IC5") (pin "2") (pinfunction "1D_2") (pintype "input"))
      (node (ref "IC6") (pin "2") (pinfunction "1D_2") (pintype "input"))
      (node (ref "IC7") (pin "2") (pinfunction "1D_2") (pintype "input"))
      (node (ref "IC8") (pin "2") (pinfunction "1D_2") (pintype "input"))
      (node (ref "IC9") (pin "2") (pinfunction "1D_2") (pintype "input"))
    )
    (net (code "95") (name "Net-(IC14-(ADC1)PA1)") (class "Default")
      (node (ref "IC14") (pin "36") (pinfunction "(ADC1)PA1_36") (pintype "bidirectional"))
      (node (ref "IC2") (pin "3") (pinfunction "2D_3") (pintype "input"))
      (node (ref "IC3") (pin "3") (pinfunction "2D_3") (pintype "input"))
      (node (ref "IC4") (pin "3") (pinfunction "2D_3") (pintype "input"))
      (node (ref "IC5") (pin "3") (pinfunction "2D_3") (pintype "input"))
      (node (ref "IC6") (pin "3") (pinfunction "2D_3") (pintype "input"))
      (node (ref "IC7") (pin "3") (pinfunction "2D_3") (pintype "input"))
      (node (ref "IC8") (pin "3") (pinfunction "2D_3") (pintype "input"))
      (node (ref "IC9") (pin "3") (pinfunction "2D_3") (pintype "input"))
    )
    (net (code "96") (name "Net-(IC14-(ADC2)PA2)") (class "Default")
      (node (ref "IC14") (pin "35") (pinfunction "(ADC2)PA2_35") (pintype "bidirectional"))
      (node (ref "IC2") (pin "4") (pinfunction "3D_4") (pintype "input"))
      (node (ref "IC3") (pin "4") (pinfunction "3D_4") (pintype "input"))
      (node (ref "IC4") (pin "4") (pinfunction "3D_4") (pintype "input"))
      (node (ref "IC5") (pin "4") (pinfunction "3D_4") (pintype "input"))
      (node (ref "IC6") (pin "4") (pinfunction "3D_4") (pintype "input"))
      (node (ref "IC7") (pin "4") (pinfunction "3D_4") (pintype "input"))
      (node (ref "IC8") (pin "4") (pinfunction "3D_4") (pintype "input"))
      (node (ref "IC9") (pin "4") (pinfunction "3D_4") (pintype "input"))
    )
    (net (code "97") (name "Net-(IC14-(ADC3)PA3)") (class "Default")
      (node (ref "IC14") (pin "34") (pinfunction "(ADC3)PA3_34") (pintype "bidirectional"))
      (node (ref "IC2") (pin "5") (pinfunction "4D_5") (pintype "input"))
      (node (ref "IC3") (pin "5") (pinfunction "4D_5") (pintype "input"))
      (node (ref "IC4") (pin "5") (pinfunction "4D_5") (pintype "input"))
      (node (ref "IC5") (pin "5") (pinfunction "4D_5") (pintype "input"))
      (node (ref "IC6") (pin "5") (pinfunction "4D_5") (pintype "input"))
      (node (ref "IC7") (pin "5") (pinfunction "4D_5") (pintype "input"))
      (node (ref "IC8") (pin "5") (pinfunction "4D_5") (pintype "input"))
      (node (ref "IC9") (pin "5") (pinfunction "4D_5") (pintype "input"))
    )
    (net (code "98") (name "Net-(IC14-(ADC4)PA4)") (class "Default")
      (node (ref "IC14") (pin "33") (pinfunction "(ADC4)PA4_33") (pintype "bidirectional"))
      (node (ref "IC2") (pin "6") (pinfunction "5D_6") (pintype "input"))
      (node (ref "IC3") (pin "6") (pinfunction "5D_6") (pintype "input"))
      (node (ref "IC4") (pin "6") (pinfunction "5D_6") (pintype "input"))
      (node (ref "IC5") (pin "6") (pinfunction "5D_6") (pintype "input"))
      (node (ref "IC6") (pin "6") (pinfunction "5D_6") (pintype "input"))
      (node (ref "IC7") (pin "6") (pinfunction "5D_6") (pintype "input"))
      (node (ref "IC8") (pin "6") (pinfunction "5D_6") (pintype "input"))
      (node (ref "IC9") (pin "6") (pinfunction "5D_6") (pintype "input"))
    )
    (net (code "99") (name "Net-(IC14-(ADC5)PA5)") (class "Default")
      (node (ref "IC14") (pin "32") (pinfunction "(ADC5)PA5_32") (pintype "bidirectional"))
      (node (ref "IC2") (pin "7") (pinfunction "6D_7") (pintype "input"))
      (node (ref "IC3") (pin "7") (pinfunction "6D_7") (pintype "input"))
      (node (ref "IC4") (pin "7") (pinfunction "6D_7") (pintype "input"))
      (node (ref "IC5") (pin "7") (pinfunction "6D_7") (pintype "input"))
      (node (ref "IC6") (pin "7") (pinfunction "6D_7") (pintype "input"))
      (node (ref "IC7") (pin "7") (pinfunction "6D_7") (pintype "input"))
      (node (ref "IC8") (pin "7") (pinfunction "6D_7") (pintype "input"))
      (node (ref "IC9") (pin "7") (pinfunction "6D_7") (pintype "input"))
    )
    (net (code "100") (name "Net-(IC14-(ADC6)PA6)") (class "Default")
      (node (ref "IC14") (pin "31") (pinfunction "(ADC6)PA6_31") (pintype "bidirectional"))
      (node (ref "IC2") (pin "8") (pinfunction "7D_8") (pintype "input"))
      (node (ref "IC3") (pin "8") (pinfunction "7D_8") (pintype "input"))
      (node (ref "IC4") (pin "8") (pinfunction "7D_8") (pintype "input"))
      (node (ref "IC5") (pin "8") (pinfunction "7D_8") (pintype "input"))
      (node (ref "IC6") (pin "8") (pinfunction "7D_8") (pintype "input"))
      (node (ref "IC7") (pin "8") (pinfunction "7D_8") (pintype "input"))
      (node (ref "IC8") (pin "8") (pinfunction "7D_8") (pintype "input"))
      (node (ref "IC9") (pin "8") (pinfunction "7D_8") (pintype "input"))
    )
    (net (code "101") (name "Net-(IC14-(ADC7)PA7)") (class "Default")
      (node (ref "IC14") (pin "30") (pinfunction "(ADC7)PA7_30") (pintype "bidirectional"))
      (node (ref "IC2") (pin "9") (pinfunction "8D_9") (pintype "input"))
      (node (ref "IC3") (pin "9") (pinfunction "8D_9") (pintype "input"))
      (node (ref "IC4") (pin "9") (pinfunction "8D_9") (pintype "input"))
      (node (ref "IC5") (pin "9") (pinfunction "8D_9") (pintype "input"))
      (node (ref "IC6") (pin "9") (pinfunction "8D_9") (pintype "input"))
      (node (ref "IC7") (pin "9") (pinfunction "8D_9") (pintype "input"))
      (node (ref "IC8") (pin "9") (pinfunction "8D_9") (pintype "input"))
      (node (ref "IC9") (pin "9") (pinfunction "8D_9") (pintype "input"))
    )
    (net (code "102") (name "Net-(IC14-(AIN0{slash}INT2)PB2)") (class "Default")
      (node (ref "IC14") (pin "42") (pinfunction "(AIN0/INT2)PB2_42") (pintype "bidirectional"))
      (node (ref "IC8") (pin "11") (pinfunction "C_11") (pintype "input"))
    )
    (net (code "103") (name "Net-(IC14-(AIN1{slash}OC0)PB3)") (class "Default")
      (node (ref "IC14") (pin "43") (pinfunction "(AIN1/OC0)PB3_43") (pintype "bidirectional"))
      (node (ref "R9") (pin "1") (pinfunction "1_1") (pintype "passive"))
    )
    (net (code "104") (name "Net-(IC14-(ICP)PD6)") (class "Default")
      (node (ref "IC14") (pin "15") (pinfunction "(ICP)PD6_15") (pintype "bidirectional"))
      (node (ref "R3") (pin "1") (pinfunction "1_1") (pintype "passive"))
    )
    (net (code "105") (name "Net-(IC14-(INT0)PD2)") (class "Default")
      (node (ref "IC14") (pin "11") (pinfunction "(INT0)PD2_11") (pintype "bidirectional"))
      (node (ref "R7") (pin "1") (pinfunction "1_1") (pintype "passive"))
    )
    (net (code "106") (name "Net-(IC14-(INT1)PD3)") (class "Default")
      (node (ref "IC14") (pin "12") (pinfunction "(INT1)PD3_12") (pintype "bidirectional"))
      (node (ref "R6") (pin "1") (pinfunction "1_1") (pintype "passive"))
    )
    (net (code "107") (name "Net-(IC14-(MISO)PB6)") (class "Default")
      (node (ref "IC14") (pin "2") (pinfunction "(MISO)PB6_2") (pintype "bidirectional"))
      (node (ref "JP3") (pin "9") (pinfunction "MISO_9") (pintype "bidirectional"))
    )
    (net (code "108") (name "Net-(IC14-(MOSI)PB5)") (class "Default")
      (node (ref "IC14") (pin "1") (pinfunction "(MOSI)PB5_1") (pintype "bidirectional"))
      (node (ref "JP3") (pin "1") (pinfunction "MOSI_1") (pintype "bidirectional"))
    )
    (net (code "109") (name "Net-(IC14-(OC1A)PD5)") (class "Default")
      (node (ref "IC14") (pin "14") (pinfunction "(OC1A)PD5_14") (pintype "bidirectional"))
      (node (ref "R4") (pin "1") (pinfunction "1_1") (pintype "passive"))
    )
    (net (code "110") (name "Net-(IC14-(OC1B)PD4)") (class "Default")
      (node (ref "IC14") (pin "13") (pinfunction "(OC1B)PD4_13") (pintype "bidirectional"))
      (node (ref "R5") (pin "1") (pinfunction "1_1") (pintype "passive"))
    )
    (net (code "111") (name "Net-(IC14-(OC2)PD7)") (class "Default")
      (node (ref "IC14") (pin "16") (pinfunction "(OC2)PD7_16") (pintype "bidirectional"))
      (node (ref "R2") (pin "1") (pinfunction "1_1") (pintype "passive"))
    )
    (net (code "112") (name "Net-(IC14-(SCK)PB7)") (class "Default")
      (node (ref "IC14") (pin "3") (pinfunction "(SCK)PB7_3") (pintype "bidirectional"))
      (node (ref "JP3") (pin "7") (pinfunction "SCK_7") (pintype "input"))
    )
    (net (code "113") (name "Net-(IC14-(SS)PB4)") (class "Default")
      (node (ref "IC14") (pin "44") (pinfunction "(SS)PB4_44") (pintype "bidirectional"))
      (node (ref "R8") (pin "1") (pinfunction "1_1") (pintype "passive"))
    )
    (net (code "114") (name "Net-(IC14-(T0{slash}XCK)PB0)") (class "Default")
      (node (ref "IC14") (pin "40") (pinfunction "(T0/XCK)PB0_40") (pintype "bidirectional"))
      (node (ref "R20") (pin "2") (pinfunction "2_2") (pintype "passive"))
      (node (ref "U$74") (pin "A") (pinfunction "A_A") (pintype "bidirectional"))
      (node (ref "U$74") (pin "A2") (pinfunction "A2_A2") (pintype "bidirectional"))
    )
    (net (code "115") (name "Net-(IC14-(T1)PB1)") (class "Default")
      (node (ref "IC14") (pin "41") (pinfunction "(T1)PB1_41") (pintype "bidirectional"))
      (node (ref "IC9") (pin "11") (pinfunction "C_11") (pintype "input"))
    )
    (net (code "116") (name "Net-(IC14-(TCK)PC2)") (class "Default")
      (node (ref "IC14") (pin "21") (pinfunction "(TCK)PC2_21") (pintype "bidirectional"))
      (node (ref "IC6") (pin "11") (pinfunction "C_11") (pintype "input"))
    )
    (net (code "117") (name "Net-(IC14-(TDI)PC5)") (class "Default")
      (node (ref "IC14") (pin "24") (pinfunction "(TDI)PC5_24") (pintype "bidirectional"))
      (node (ref "IC3") (pin "11") (pinfunction "C_11") (pintype "input"))
    )
    (net (code "118") (name "Net-(IC14-(TDO)PC4)") (class "Default")
      (node (ref "IC14") (pin "23") (pinfunction "(TDO)PC4_23") (pintype "bidirectional"))
      (node (ref "IC4") (pin "11") (pinfunction "C_11") (pintype "input"))
    )
    (net (code "119") (name "Net-(IC14-(TMS)PC3)") (class "Default")
      (node (ref "IC14") (pin "22") (pinfunction "(TMS)PC3_22") (pintype "bidirectional"))
      (node (ref "IC5") (pin "11") (pinfunction "C_11") (pintype "input"))
    )
    (net (code "120") (name "Net-(IC14-(TOSC1)PC6)") (class "Default")
      (node (ref "IC14") (pin "25") (pinfunction "(TOSC1)PC6_25") (pintype "bidirectional"))
      (node (ref "IC2") (pin "11") (pinfunction "C_11") (pintype "input"))
    )
    (net (code "121") (name "Net-(IC14-(TOSC2)PC7)") (class "Default")
      (node (ref "IC14") (pin "26") (pinfunction "(TOSC2)PC7_26") (pintype "bidirectional"))
      (node (ref "IC7") (pin "11") (pinfunction "C_11") (pintype "input"))
    )
    (net (code "122") (name "Net-(IC14-AREF)") (class "Default")
      (node (ref "C2") (pin "1") (pinfunction "1_1") (pintype "passive"))
      (node (ref "IC14") (pin "29") (pinfunction "AREF_29") (pintype "passive"))
    )
    (net (code "123") (name "Net-(IC14-RESET)") (class "Default")
      (node (ref "IC14") (pin "4") (pinfunction "RESET_4") (pintype "input"))
      (node (ref "JP3") (pin "5") (pinfunction "RESET_5") (pintype "input"))
      (node (ref "R1") (pin "2") (pinfunction "2_2") (pintype "passive"))
    )
    (net (code "124") (name "Net-(IC14-XTAL1)") (class "Default")
      (node (ref "C4") (pin "2") (pinfunction "2_2") (pintype "passive"))
      (node (ref "IC14") (pin "8") (pinfunction "XTAL1_8") (pintype "bidirectional"))
      (node (ref "Q1") (pin "1") (pinfunction "1_1") (pintype "passive"))
    )
    (net (code "125") (name "Net-(IC14-XTAL2)") (class "Default")
      (node (ref "C5") (pin "2") (pinfunction "2_2") (pintype "passive"))
      (node (ref "IC14") (pin "7") (pinfunction "XTAL2_7") (pintype "bidirectional"))
      (node (ref "Q1") (pin "2") (pinfunction "2_2") (pintype "passive"))
    )
    (net (code "126") (name "Net-(JP1-P0)") (class "Default")
      (node (ref "JP1") (pin "1") (pinfunction "P0_1") (pintype "bidirectional"))
      (node (ref "U$66") (pin "2") (pinfunction "D_2") (pintype "passive"))
    )
    (net (code "127") (name "Net-(JP1-P1)") (class "Default")
      (node (ref "JP1") (pin "2") (pinfunction "P1_2") (pintype "bidirectional"))
      (node (ref "U$67") (pin "2") (pinfunction "D_2") (pintype "passive"))
    )
    (net (code "128") (name "Net-(JP1-P2)") (class "Default")
      (node (ref "JP1") (pin "3") (pinfunction "P2_3") (pintype "bidirectional"))
      (node (ref "U$68") (pin "2") (pinfunction "D_2") (pintype "passive"))
    )
    (net (code "129") (name "Net-(JP1-P3)") (class "Default")
      (node (ref "JP1") (pin "4") (pinfunction "P3_4") (pintype "bidirectional"))
      (node (ref "U$69") (pin "2") (pinfunction "D_2") (pintype "passive"))
    )
    (net (code "130") (name "Net-(JP1-P4)") (class "Default")
      (node (ref "JP1") (pin "5") (pinfunction "P4_5") (pintype "bidirectional"))
      (node (ref "U$70") (pin "2") (pinfunction "D_2") (pintype "passive"))
    )
    (net (code "131") (name "Net-(JP1-P5)") (class "Default")
      (node (ref "JP1") (pin "6") (pinfunction "P5_6") (pintype "bidirectional"))
      (node (ref "U$71") (pin "2") (pinfunction "D_2") (pintype "passive"))
    )
    (net (code "132") (name "Net-(JP1-P6)") (class "Default")
      (node (ref "JP1") (pin "7") (pinfunction "P6_7") (pintype "bidirectional"))
      (node (ref "U$72") (pin "2") (pinfunction "D_2") (pintype "passive"))
    )
    (net (code "133") (name "Net-(JP1-P7)") (class "Default")
      (node (ref "JP1") (pin "8") (pinfunction "P7_8") (pintype "bidirectional"))
      (node (ref "U$73") (pin "2") (pinfunction "D_2") (pintype "passive"))
    )
    (net (code "134") (name "Net-(LED1-PadC)") (class "Default")
      (node (ref "LED1") (pin "C") (pinfunction "C_C") (pintype "passive"))
      (node (ref "R31") (pin "2") (pinfunction "2_2") (pintype "passive"))
    )
    (net (code "135") (name "Net-(LED65-PadC)") (class "Default")
      (node (ref "LED65") (pin "C") (pinfunction "C_C") (pintype "passive"))
      (node (ref "R21") (pin "2") (pinfunction "2_2") (pintype "passive"))
    )
    (net (code "136") (name "Net-(R11-Pad2)") (class "Default")
      (node (ref "R11") (pin "2") (pinfunction "2_2") (pintype "passive"))
      (node (ref "X2") (pin "1") (pinfunction "1_1") (pintype "input"))
    )
    (net (code "137") (name "Net-(R22-Pad2)") (class "Default")
      (node (ref "R22") (pin "2") (pinfunction "2_2") (pintype "passive"))
      (node (ref "SV1") (pin "9") (pinfunction "9_9") (pintype "passive"))
    )
    (net (code "138") (name "Net-(R32-Pad2)") (class "Default")
      (node (ref "R32") (pin "2") (pinfunction "2_2") (pintype "passive"))
      (node (ref "SV1") (pin "11") (pinfunction "11_11") (pintype "passive"))
    )
    (net (code "139") (name "Net-(R33-Pad2)") (class "Default")
      (node (ref "R33") (pin "2") (pinfunction "2_2") (pintype "passive"))
      (node (ref "SV1") (pin "13") (pinfunction "13_13") (pintype "passive"))
    )
    (net (code "140") (name "Net-(R34-Pad2)") (class "Default")
      (node (ref "R34") (pin "2") (pinfunction "2_2") (pintype "passive"))
      (node (ref "SV1") (pin "15") (pinfunction "15_15") (pintype "passive"))
    )
    (net (code "141") (name "Net-(R35-Pad2)") (class "Default")
      (node (ref "R35") (pin "2") (pinfunction "2_2") (pintype "passive"))
      (node (ref "SV1") (pin "17") (pinfunction "17_17") (pintype "passive"))
    )
    (net (code "142") (name "Net-(R36-Pad2)") (class "Default")
      (node (ref "R36") (pin "2") (pinfunction "2_2") (pintype "passive"))
      (node (ref "SV1") (pin "19") (pinfunction "19_19") (pintype "passive"))
    )
    (net (code "143") (name "Net-(R37-Pad2)") (class "Default")
      (node (ref "R37") (pin "2") (pinfunction "2_2") (pintype "passive"))
      (node (ref "SV1") (pin "21") (pinfunction "21_21") (pintype "passive"))
    )
    (net (code "144") (name "Net-(R38-Pad2)") (class "Default")
      (node (ref "R38") (pin "2") (pinfunction "2_2") (pintype "passive"))
      (node (ref "SV1") (pin "23") (pinfunction "23_23") (pintype "passive"))
    )
    (net (code "145") (name "Net-(R103-Pad2)") (class "Default")
      (node (ref "R103") (pin "2") (pinfunction "2_2") (pintype "passive"))
      (node (ref "SV1") (pin "25") (pinfunction "25_25") (pintype "passive"))
    )
    (net (code "146") (name "Net-(R104-Pad2)") (class "Default")
      (node (ref "R104") (pin "2") (pinfunction "2_2") (pintype "passive"))
      (node (ref "SV1") (pin "27") (pinfunction "27_27") (pintype "passive"))
    )
    (net (code "147") (name "Net-(R105-Pad2)") (class "Default")
      (node (ref "R105") (pin "2") (pinfunction "2_2") (pintype "passive"))
      (node (ref "SV1") (pin "29") (pinfunction "29_29") (pintype "passive"))
    )
    (net (code "148") (name "Net-(R106-Pad2)") (class "Default")
      (node (ref "R106") (pin "2") (pinfunction "2_2") (pintype "passive"))
      (node (ref "SV1") (pin "31") (pinfunction "31_31") (pintype "passive"))
    )
    (net (code "149") (name "Net-(R107-Pad2)") (class "Default")
      (node (ref "R107") (pin "2") (pinfunction "2_2") (pintype "passive"))
      (node (ref "SV1") (pin "7") (pinfunction "7_7") (pintype "passive"))
    )
    (net (code "150") (name "Net-(R108-Pad2)") (class "Default")
      (node (ref "R108") (pin "2") (pinfunction "2_2") (pintype "passive"))
      (node (ref "SV1") (pin "5") (pinfunction "5_5") (pintype "passive"))
    )
    (net (code "151") (name "Net-(R109-Pad2)") (class "Default")
      (node (ref "R109") (pin "2") (pinfunction "2_2") (pintype "passive"))
      (node (ref "SV1") (pin "3") (pinfunction "3_3") (pintype "passive"))
    )
    (net (code "152") (name "Net-(R110-Pad2)") (class "Default")
      (node (ref "R110") (pin "2") (pinfunction "2_2") (pintype "passive"))
      (node (ref "SV1") (pin "1") (pinfunction "1_1") (pintype "passive"))
    )
    (net (code "153") (name "Net-(R111-Pad2)") (class "Default")
      (node (ref "R111") (pin "2") (pinfunction "2_2") (pintype "passive"))
      (node (ref "SV1") (pin "33") (pinfunction "33_33") (pintype "passive"))
    )
    (net (code "154") (name "Net-(R112-Pad2)") (class "Default")
      (node (ref "R112") (pin "2") (pinfunction "2_2") (pintype "passive"))
      (node (ref "SV1") (pin "35") (pinfunction "35_35") (pintype "passive"))
    )
    (net (code "155") (name "Net-(R113-Pad2)") (class "Default")
      (node (ref "R113") (pin "2") (pinfunction "2_2") (pintype "passive"))
      (node (ref "SV1") (pin "37") (pinfunction "37_37") (pintype "passive"))
    )
    (net (code "156") (name "Net-(R114-Pad2)") (class "Default")
      (node (ref "R114") (pin "2") (pinfunction "2_2") (pintype "passive"))
      (node (ref "SV1") (pin "39") (pinfunction "39_39") (pintype "passive"))
    )
    (net (code "157") (name "Net-(R115-Pad2)") (class "Default")
      (node (ref "R115") (pin "2") (pinfunction "2_2") (pintype "passive"))
      (node (ref "SV1") (pin "41") (pinfunction "41_41") (pintype "passive"))
    )
    (net (code "158") (name "Net-(R116-Pad2)") (class "Default")
      (node (ref "R116") (pin "2") (pinfunction "2_2") (pintype "passive"))
      (node (ref "SV1") (pin "43") (pinfunction "43_43") (pintype "passive"))
    )
    (net (code "159") (name "Net-(R117-Pad2)") (class "Default")
      (node (ref "R117") (pin "2") (pinfunction "2_2") (pintype "passive"))
      (node (ref "SV1") (pin "45") (pinfunction "45_45") (pintype "passive"))
    )
    (net (code "160") (name "Net-(R118-Pad2)") (class "Default")
      (node (ref "R118") (pin "2") (pinfunction "2_2") (pintype "passive"))
      (node (ref "SV1") (pin "47") (pinfunction "47_47") (pintype "passive"))
    )
    (net (code "161") (name "Net-(R119-Pad2)") (class "Default")
      (node (ref "R119") (pin "2") (pinfunction "2_2") (pintype "passive"))
      (node (ref "SV1") (pin "49") (pinfunction "49_49") (pintype "passive"))
    )
    (net (code "162") (name "Net-(R120-Pad2)") (class "Default")
      (node (ref "R120") (pin "2") (pinfunction "2_2") (pintype "passive"))
      (node (ref "SV1") (pin "51") (pinfunction "51_51") (pintype "passive"))
    )
    (net (code "163") (name "Net-(R121-Pad2)") (class "Default")
      (node (ref "R121") (pin "2") (pinfunction "2_2") (pintype "passive"))
      (node (ref "SV1") (pin "55") (pinfunction "55_55") (pintype "passive"))
    )
    (net (code "164") (name "Net-(R122-Pad2)") (class "Default")
      (node (ref "R122") (pin "2") (pinfunction "2_2") (pintype "passive"))
      (node (ref "SV1") (pin "53") (pinfunction "53_53") (pintype "passive"))
    )
    (net (code "165") (name "Net-(R123-Pad2)") (class "Default")
      (node (ref "R123") (pin "2") (pinfunction "2_2") (pintype "passive"))
      (node (ref "SV1") (pin "57") (pinfunction "57_57") (pintype "passive"))
    )
    (net (code "166") (name "Net-(R124-Pad2)") (class "Default")
      (node (ref "R124") (pin "2") (pinfunction "2_2") (pintype "passive"))
      (node (ref "SV1") (pin "59") (pinfunction "59_59") (pintype "passive"))
    )
    (net (code "167") (name "Net-(R125-Pad2)") (class "Default")
      (node (ref "R125") (pin "2") (pinfunction "2_2") (pintype "passive"))
      (node (ref "SV1") (pin "61") (pinfunction "61_61") (pintype "passive"))
    )
    (net (code "168") (name "Net-(R126-Pad2)") (class "Default")
      (node (ref "R126") (pin "2") (pinfunction "2_2") (pintype "passive"))
      (node (ref "SV1") (pin "63") (pinfunction "63_63") (pintype "passive"))
    )
    (net (code "169") (name "Net-(R127-Pad1)") (class "Default")
      (node (ref "R127") (pin "1") (pinfunction "1_1") (pintype "passive"))
      (node (ref "SV1") (pin "6") (pinfunction "6_6") (pintype "passive"))
    )
    (net (code "170") (name "Net-(R128-Pad1)") (class "Default")
      (node (ref "R128") (pin "1") (pinfunction "1_1") (pintype "passive"))
      (node (ref "SV1") (pin "8") (pinfunction "8_8") (pintype "passive"))
    )
    (net (code "171") (name "Net-(R129-Pad1)") (class "Default")
      (node (ref "R129") (pin "1") (pinfunction "1_1") (pintype "passive"))
      (node (ref "SV1") (pin "10") (pinfunction "10_10") (pintype "passive"))
    )
    (net (code "172") (name "Net-(R130-Pad1)") (class "Default")
      (node (ref "R130") (pin "1") (pinfunction "1_1") (pintype "passive"))
      (node (ref "SV1") (pin "12") (pinfunction "12_12") (pintype "passive"))
    )
    (net (code "173") (name "Net-(R131-Pad1)") (class "Default")
      (node (ref "R131") (pin "1") (pinfunction "1_1") (pintype "passive"))
      (node (ref "SV1") (pin "14") (pinfunction "14_14") (pintype "passive"))
    )
    (net (code "174") (name "Net-(R132-Pad1)") (class "Default")
      (node (ref "R132") (pin "1") (pinfunction "1_1") (pintype "passive"))
      (node (ref "SV1") (pin "16") (pinfunction "16_16") (pintype "passive"))
    )
    (net (code "175") (name "Net-(R133-Pad1)") (class "Default")
      (node (ref "R133") (pin "1") (pinfunction "1_1") (pintype "passive"))
      (node (ref "SV1") (pin "18") (pinfunction "18_18") (pintype "passive"))
    )
    (net (code "176") (name "Net-(R134-Pad1)") (class "Default")
      (node (ref "R134") (pin "1") (pinfunction "1_1") (pintype "passive"))
      (node (ref "SV1") (pin "20") (pinfunction "20_20") (pintype "passive"))
    )
    (net (code "177") (name "Net-(R135-Pad1)") (class "Default")
      (node (ref "R135") (pin "1") (pinfunction "1_1") (pintype "passive"))
      (node (ref "SV1") (pin "22") (pinfunction "22_22") (pintype "passive"))
    )
    (net (code "178") (name "Net-(R136-Pad1)") (class "Default")
      (node (ref "R136") (pin "1") (pinfunction "1_1") (pintype "passive"))
      (node (ref "SV1") (pin "24") (pinfunction "24_24") (pintype "passive"))
    )
    (net (code "179") (name "Net-(R137-Pad1)") (class "Default")
      (node (ref "R137") (pin "1") (pinfunction "1_1") (pintype "passive"))
      (node (ref "SV1") (pin "26") (pinfunction "26_26") (pintype "passive"))
    )
    (net (code "180") (name "Net-(R138-Pad1)") (class "Default")
      (node (ref "R138") (pin "1") (pinfunction "1_1") (pintype "passive"))
      (node (ref "SV1") (pin "28") (pinfunction "28_28") (pintype "passive"))
    )
    (net (code "181") (name "Net-(R139-Pad1)") (class "Default")
      (node (ref "R139") (pin "1") (pinfunction "1_1") (pintype "passive"))
      (node (ref "SV1") (pin "30") (pinfunction "30_30") (pintype "passive"))
    )
    (net (code "182") (name "Net-(R140-Pad1)") (class "Default")
      (node (ref "R140") (pin "1") (pinfunction "1_1") (pintype "passive"))
      (node (ref "SV1") (pin "32") (pinfunction "32_32") (pintype "passive"))
    )
    (net (code "183") (name "Net-(R141-Pad1)") (class "Default")
      (node (ref "R141") (pin "1") (pinfunction "1_1") (pintype "passive"))
      (node (ref "SV1") (pin "34") (pinfunction "34_34") (pintype "passive"))
    )
    (net (code "184") (name "Net-(R142-Pad1)") (class "Default")
      (node (ref "R142") (pin "1") (pinfunction "1_1") (pintype "passive"))
      (node (ref "SV1") (pin "36") (pinfunction "36_36") (pintype "passive"))
    )
    (net (code "185") (name "Net-(R143-Pad1)") (class "Default")
      (node (ref "R143") (pin "1") (pinfunction "1_1") (pintype "passive"))
      (node (ref "SV1") (pin "38") (pinfunction "38_38") (pintype "passive"))
    )
    (net (code "186") (name "Net-(R144-Pad1)") (class "Default")
      (node (ref "R144") (pin "1") (pinfunction "1_1") (pintype "passive"))
      (node (ref "SV1") (pin "40") (pinfunction "40_40") (pintype "passive"))
    )
    (net (code "187") (name "Net-(R145-Pad1)") (class "Default")
      (node (ref "R145") (pin "1") (pinfunction "1_1") (pintype "passive"))
      (node (ref "SV1") (pin "42") (pinfunction "42_42") (pintype "passive"))
    )
    (net (code "188") (name "Net-(R146-Pad1)") (class "Default")
      (node (ref "R146") (pin "1") (pinfunction "1_1") (pintype "passive"))
      (node (ref "SV1") (pin "44") (pinfunction "44_44") (pintype "passive"))
    )
    (net (code "189") (name "Net-(R147-Pad1)") (class "Default")
      (node (ref "R147") (pin "1") (pinfunction "1_1") (pintype "passive"))
      (node (ref "SV1") (pin "46") (pinfunction "46_46") (pintype "passive"))
    )
    (net (code "190") (name "Net-(R148-Pad1)") (class "Default")
      (node (ref "R148") (pin "1") (pinfunction "1_1") (pintype "passive"))
      (node (ref "SV1") (pin "48") (pinfunction "48_48") (pintype "passive"))
    )
    (net (code "191") (name "Net-(R149-Pad1)") (class "Default")
      (node (ref "R149") (pin "1") (pinfunction "1_1") (pintype "passive"))
      (node (ref "SV1") (pin "50") (pinfunction "50_50") (pintype "passive"))
    )
    (net (code "192") (name "Net-(R150-Pad1)") (class "Default")
      (node (ref "R150") (pin "1") (pinfunction "1_1") (pintype "passive"))
      (node (ref "SV1") (pin "52") (pinfunction "52_52") (pintype "passive"))
    )
    (net (code "193") (name "Net-(R151-Pad1)") (class "Default")
      (node (ref "R151") (pin "1") (pinfunction "1_1") (pintype "passive"))
      (node (ref "SV1") (pin "54") (pinfunction "54_54") (pintype "passive"))
    )
    (net (code "194") (name "Net-(R152-Pad1)") (class "Default")
      (node (ref "R152") (pin "1") (pinfunction "1_1") (pintype "passive"))
      (node (ref "SV1") (pin "56") (pinfunction "56_56") (pintype "passive"))
    )
    (net (code "195") (name "Net-(R153-Pad1)") (class "Default")
      (node (ref "R153") (pin "1") (pinfunction "1_1") (pintype "passive"))
      (node (ref "SV1") (pin "58") (pinfunction "58_58") (pintype "passive"))
    )
    (net (code "196") (name "Net-(R154-Pad1)") (class "Default")
      (node (ref "R154") (pin "1") (pinfunction "1_1") (pintype "passive"))
      (node (ref "SV1") (pin "4") (pinfunction "4_4") (pintype "passive"))
    )
    (net (code "197") (name "Net-(R155-Pad1)") (class "Default")
      (node (ref "R155") (pin "1") (pinfunction "1_1") (pintype "passive"))
      (node (ref "SV1") (pin "2") (pinfunction "2_2") (pintype "passive"))
    )
    (net (code "198") (name "Net-(R156-Pad1)") (class "Default")
      (node (ref "R156") (pin "1") (pinfunction "1_1") (pintype "passive"))
      (node (ref "SV1") (pin "60") (pinfunction "60_60") (pintype "passive"))
    )
    (net (code "199") (name "Net-(R157-Pad1)") (class "Default")
      (node (ref "R157") (pin "1") (pinfunction "1_1") (pintype "passive"))
      (node (ref "SV1") (pin "62") (pinfunction "62_62") (pintype "passive"))
    )
    (net (code "200") (name "Net-(R158-Pad1)") (class "Default")
      (node (ref "R158") (pin "1") (pinfunction "1_1") (pintype "passive"))
      (node (ref "SV1") (pin "64") (pinfunction "64_64") (pintype "passive"))
    )
    (net (code "201") (name "Net-(U$1-L)") (class "Default")
      (node (ref "R17") (pin "1") (pinfunction "1_1") (pintype "passive"))
      (node (ref "U$1") (pin "LEFT") (pinfunction "L_LEFT") (pintype "bidirectional"))
    )
    (net (code "202") (name "Net-(U$1-R)") (class "Default")
      (node (ref "R16") (pin "1") (pinfunction "1_1") (pintype "passive"))
      (node (ref "U$1") (pin "RIGHT") (pinfunction "R_RIGHT") (pintype "bidirectional"))
    )
    (net (code "203") (name "Net-(U$2-B)") (class "Default")
      (node (ref "R39") (pin "2") (pinfunction "2_2") (pintype "passive"))
      (node (ref "U$2") (pin "P$1") (pinfunction "B_P$1") (pintype "passive"))
    )
    (net (code "204") (name "Net-(U$2-C)") (class "Default")
      (node (ref "R110") (pin "1") (pinfunction "1_1") (pintype "passive"))
      (node (ref "U$2") (pin "P$3") (pinfunction "C_P$3") (pintype "passive"))
    )
    (net (code "205") (name "Net-(U$3-B)") (class "Default")
      (node (ref "R40") (pin "2") (pinfunction "2_2") (pintype "passive"))
      (node (ref "U$3") (pin "P$1") (pinfunction "B_P$1") (pintype "passive"))
    )
    (net (code "206") (name "Net-(U$3-C)") (class "Default")
      (node (ref "R154") (pin "2") (pinfunction "2_2") (pintype "passive"))
      (node (ref "U$3") (pin "P$3") (pinfunction "C_P$3") (pintype "passive"))
    )
    (net (code "207") (name "Net-(U$4-B)") (class "Default")
      (node (ref "R41") (pin "2") (pinfunction "2_2") (pintype "passive"))
      (node (ref "U$4") (pin "P$1") (pinfunction "B_P$1") (pintype "passive"))
    )
    (net (code "208") (name "Net-(U$4-C)") (class "Default")
      (node (ref "R108") (pin "1") (pinfunction "1_1") (pintype "passive"))
      (node (ref "U$4") (pin "P$3") (pinfunction "C_P$3") (pintype "passive"))
    )
    (net (code "209") (name "Net-(U$5-B)") (class "Default")
      (node (ref "R42") (pin "2") (pinfunction "2_2") (pintype "passive"))
      (node (ref "U$5") (pin "P$1") (pinfunction "B_P$1") (pintype "passive"))
    )
    (net (code "210") (name "Net-(U$5-C)") (class "Default")
      (node (ref "R155") (pin "2") (pinfunction "2_2") (pintype "passive"))
      (node (ref "U$5") (pin "P$3") (pinfunction "C_P$3") (pintype "passive"))
    )
    (net (code "211") (name "Net-(U$6-B)") (class "Default")
      (node (ref "R43") (pin "2") (pinfunction "2_2") (pintype "passive"))
      (node (ref "U$6") (pin "P$1") (pinfunction "B_P$1") (pintype "passive"))
    )
    (net (code "212") (name "Net-(U$6-C)") (class "Default")
      (node (ref "R109") (pin "1") (pinfunction "1_1") (pintype "passive"))
      (node (ref "U$6") (pin "P$3") (pinfunction "C_P$3") (pintype "passive"))
    )
    (net (code "213") (name "Net-(U$7-B)") (class "Default")
      (node (ref "R44") (pin "2") (pinfunction "2_2") (pintype "passive"))
      (node (ref "U$7") (pin "P$1") (pinfunction "B_P$1") (pintype "passive"))
    )
    (net (code "214") (name "Net-(U$7-C)") (class "Default")
      (node (ref "R127") (pin "2") (pinfunction "2_2") (pintype "passive"))
      (node (ref "U$7") (pin "P$3") (pinfunction "C_P$3") (pintype "passive"))
    )
    (net (code "215") (name "Net-(U$8-B)") (class "Default")
      (node (ref "R45") (pin "2") (pinfunction "2_2") (pintype "passive"))
      (node (ref "U$8") (pin "P$1") (pinfunction "B_P$1") (pintype "passive"))
    )
    (net (code "216") (name "Net-(U$8-C)") (class "Default")
      (node (ref "R107") (pin "1") (pinfunction "1_1") (pintype "passive"))
      (node (ref "U$8") (pin "P$3") (pinfunction "C_P$3") (pintype "passive"))
    )
    (net (code "217") (name "Net-(U$9-B)") (class "Default")
      (node (ref "R46") (pin "2") (pinfunction "2_2") (pintype "passive"))
      (node (ref "U$9") (pin "P$1") (pinfunction "B_P$1") (pintype "passive"))
    )
    (net (code "218") (name "Net-(U$9-C)") (class "Default")
      (node (ref "R128") (pin "2") (pinfunction "2_2") (pintype "passive"))
      (node (ref "U$9") (pin "P$3") (pinfunction "C_P$3") (pintype "passive"))
    )
    (net (code "219") (name "Net-(U$10-B)") (class "Default")
      (node (ref "R47") (pin "2") (pinfunction "2_2") (pintype "passive"))
      (node (ref "U$10") (pin "P$1") (pinfunction "B_P$1") (pintype "passive"))
    )
    (net (code "220") (name "Net-(U$10-C)") (class "Default")
      (node (ref "R22") (pin "1") (pinfunction "1_1") (pintype "passive"))
      (node (ref "U$10") (pin "P$3") (pinfunction "C_P$3") (pintype "passive"))
    )
    (net (code "221") (name "Net-(U$11-B)") (class "Default")
      (node (ref "R48") (pin "2") (pinfunction "2_2") (pintype "passive"))
      (node (ref "U$11") (pin "P$1") (pinfunction "B_P$1") (pintype "passive"))
    )
    (net (code "222") (name "Net-(U$11-C)") (class "Default")
      (node (ref "R130") (pin "2") (pinfunction "2_2") (pintype "passive"))
      (node (ref "U$11") (pin "P$3") (pinfunction "C_P$3") (pintype "passive"))
    )
    (net (code "223") (name "Net-(U$12-B)") (class "Default")
      (node (ref "R49") (pin "2") (pinfunction "2_2") (pintype "passive"))
      (node (ref "U$12") (pin "P$1") (pinfunction "B_P$1") (pintype "passive"))
    )
    (net (code "224") (name "Net-(U$12-C)") (class "Default")
      (node (ref "R33") (pin "1") (pinfunction "1_1") (pintype "passive"))
      (node (ref "U$12") (pin "P$3") (pinfunction "C_P$3") (pintype "passive"))
    )
    (net (code "225") (name "Net-(U$13-B)") (class "Default")
      (node (ref "R50") (pin "2") (pinfunction "2_2") (pintype "passive"))
      (node (ref "U$13") (pin "P$1") (pinfunction "B_P$1") (pintype "passive"))
    )
    (net (code "226") (name "Net-(U$13-C)") (class "Default")
      (node (ref "R129") (pin "2") (pinfunction "2_2") (pintype "passive"))
      (node (ref "U$13") (pin "P$3") (pinfunction "C_P$3") (pintype "passive"))
    )
    (net (code "227") (name "Net-(U$14-B)") (class "Default")
      (node (ref "R51") (pin "2") (pinfunction "2_2") (pintype "passive"))
      (node (ref "U$14") (pin "P$1") (pinfunction "B_P$1") (pintype "passive"))
    )
    (net (code "228") (name "Net-(U$14-C)") (class "Default")
      (node (ref "R32") (pin "1") (pinfunction "1_1") (pintype "passive"))
      (node (ref "U$14") (pin "P$3") (pinfunction "C_P$3") (pintype "passive"))
    )
    (net (code "229") (name "Net-(U$15-B)") (class "Default")
      (node (ref "R52") (pin "2") (pinfunction "2_2") (pintype "passive"))
      (node (ref "U$15") (pin "P$1") (pinfunction "B_P$1") (pintype "passive"))
    )
    (net (code "230") (name "Net-(U$15-C)") (class "Default")
      (node (ref "R131") (pin "2") (pinfunction "2_2") (pintype "passive"))
      (node (ref "U$15") (pin "P$3") (pinfunction "C_P$3") (pintype "passive"))
    )
    (net (code "231") (name "Net-(U$16-B)") (class "Default")
      (node (ref "R53") (pin "2") (pinfunction "2_2") (pintype "passive"))
      (node (ref "U$16") (pin "P$1") (pinfunction "B_P$1") (pintype "passive"))
    )
    (net (code "232") (name "Net-(U$16-C)") (class "Default")
      (node (ref "R34") (pin "1") (pinfunction "1_1") (pintype "passive"))
      (node (ref "U$16") (pin "P$3") (pinfunction "C_P$3") (pintype "passive"))
    )
    (net (code "233") (name "Net-(U$17-B)") (class "Default")
      (node (ref "R54") (pin "2") (pinfunction "2_2") (pintype "passive"))
      (node (ref "U$17") (pin "P$1") (pinfunction "B_P$1") (pintype "passive"))
    )
    (net (code "234") (name "Net-(U$17-C)") (class "Default")
      (node (ref "R132") (pin "2") (pinfunction "2_2") (pintype "passive"))
      (node (ref "U$17") (pin "P$3") (pinfunction "C_P$3") (pintype "passive"))
    )
    (net (code "235") (name "Net-(U$18-B)") (class "Default")
      (node (ref "R55") (pin "2") (pinfunction "2_2") (pintype "passive"))
      (node (ref "U$18") (pin "P$1") (pinfunction "B_P$1") (pintype "passive"))
    )
    (net (code "236") (name "Net-(U$18-C)") (class "Default")
      (node (ref "R35") (pin "1") (pinfunction "1_1") (pintype "passive"))
      (node (ref "U$18") (pin "P$3") (pinfunction "C_P$3") (pintype "passive"))
    )
    (net (code "237") (name "Net-(U$19-B)") (class "Default")
      (node (ref "R56") (pin "2") (pinfunction "2_2") (pintype "passive"))
      (node (ref "U$19") (pin "P$1") (pinfunction "B_P$1") (pintype "passive"))
    )
    (net (code "238") (name "Net-(U$19-C)") (class "Default")
      (node (ref "R134") (pin "2") (pinfunction "2_2") (pintype "passive"))
      (node (ref "U$19") (pin "P$3") (pinfunction "C_P$3") (pintype "passive"))
    )
    (net (code "239") (name "Net-(U$20-B)") (class "Default")
      (node (ref "R57") (pin "2") (pinfunction "2_2") (pintype "passive"))
      (node (ref "U$20") (pin "P$1") (pinfunction "B_P$1") (pintype "passive"))
    )
    (net (code "240") (name "Net-(U$20-C)") (class "Default")
      (node (ref "R37") (pin "1") (pinfunction "1_1") (pintype "passive"))
      (node (ref "U$20") (pin "P$3") (pinfunction "C_P$3") (pintype "passive"))
    )
    (net (code "241") (name "Net-(U$21-B)") (class "Default")
      (node (ref "R58") (pin "2") (pinfunction "2_2") (pintype "passive"))
      (node (ref "U$21") (pin "P$1") (pinfunction "B_P$1") (pintype "passive"))
    )
    (net (code "242") (name "Net-(U$21-C)") (class "Default")
      (node (ref "R133") (pin "2") (pinfunction "2_2") (pintype "passive"))
      (node (ref "U$21") (pin "P$3") (pinfunction "C_P$3") (pintype "passive"))
    )
    (net (code "243") (name "Net-(U$22-B)") (class "Default")
      (node (ref "R59") (pin "2") (pinfunction "2_2") (pintype "passive"))
      (node (ref "U$22") (pin "P$1") (pinfunction "B_P$1") (pintype "passive"))
    )
    (net (code "244") (name "Net-(U$22-C)") (class "Default")
      (node (ref "R36") (pin "1") (pinfunction "1_1") (pintype "passive"))
      (node (ref "U$22") (pin "P$3") (pinfunction "C_P$3") (pintype "passive"))
    )
    (net (code "245") (name "Net-(U$23-B)") (class "Default")
      (node (ref "R60") (pin "2") (pinfunction "2_2") (pintype "passive"))
      (node (ref "U$23") (pin "P$1") (pinfunction "B_P$1") (pintype "passive"))
    )
    (net (code "246") (name "Net-(U$23-C)") (class "Default")
      (node (ref "R135") (pin "2") (pinfunction "2_2") (pintype "passive"))
      (node (ref "U$23") (pin "P$3") (pinfunction "C_P$3") (pintype "passive"))
    )
    (net (code "247") (name "Net-(U$24-B)") (class "Default")
      (node (ref "R61") (pin "2") (pinfunction "2_2") (pintype "passive"))
      (node (ref "U$24") (pin "P$1") (pinfunction "B_P$1") (pintype "passive"))
    )
    (net (code "248") (name "Net-(U$24-C)") (class "Default")
      (node (ref "R38") (pin "1") (pinfunction "1_1") (pintype "passive"))
      (node (ref "U$24") (pin "P$3") (pinfunction "C_P$3") (pintype "passive"))
    )
    (net (code "249") (name "Net-(U$25-B)") (class "Default")
      (node (ref "R62") (pin "2") (pinfunction "2_2") (pintype "passive"))
      (node (ref "U$25") (pin "P$1") (pinfunction "B_P$1") (pintype "passive"))
    )
    (net (code "250") (name "Net-(U$25-C)") (class "Default")
      (node (ref "R136") (pin "2") (pinfunction "2_2") (pintype "passive"))
      (node (ref "U$25") (pin "P$3") (pinfunction "C_P$3") (pintype "passive"))
    )
    (net (code "251") (name "Net-(U$26-B)") (class "Default")
      (node (ref "R63") (pin "2") (pinfunction "2_2") (pintype "passive"))
      (node (ref "U$26") (pin "P$1") (pinfunction "B_P$1") (pintype "passive"))
    )
    (net (code "252") (name "Net-(U$26-C)") (class "Default")
      (node (ref "R103") (pin "1") (pinfunction "1_1") (pintype "passive"))
      (node (ref "U$26") (pin "P$3") (pinfunction "C_P$3") (pintype "passive"))
    )
    (net (code "253") (name "Net-(U$27-B)") (class "Default")
      (node (ref "R64") (pin "2") (pinfunction "2_2") (pintype "passive"))
      (node (ref "U$27") (pin "P$1") (pinfunction "B_P$1") (pintype "passive"))
    )
    (net (code "254") (name "Net-(U$27-C)") (class "Default")
      (node (ref "R138") (pin "2") (pinfunction "2_2") (pintype "passive"))
      (node (ref "U$27") (pin "P$3") (pinfunction "C_P$3") (pintype "passive"))
    )
    (net (code "255") (name "Net-(U$28-B)") (class "Default")
      (node (ref "R65") (pin "2") (pinfunction "2_2") (pintype "passive"))
      (node (ref "U$28") (pin "P$1") (pinfunction "B_P$1") (pintype "passive"))
    )
    (net (code "256") (name "Net-(U$28-C)") (class "Default")
      (node (ref "R105") (pin "1") (pinfunction "1_1") (pintype "passive"))
      (node (ref "U$28") (pin "P$3") (pinfunction "C_P$3") (pintype "passive"))
    )
    (net (code "257") (name "Net-(U$29-B)") (class "Default")
      (node (ref "R66") (pin "2") (pinfunction "2_2") (pintype "passive"))
      (node (ref "U$29") (pin "P$1") (pinfunction "B_P$1") (pintype "passive"))
    )
    (net (code "258") (name "Net-(U$29-C)") (class "Default")
      (node (ref "R137") (pin "2") (pinfunction "2_2") (pintype "passive"))
      (node (ref "U$29") (pin "P$3") (pinfunction "C_P$3") (pintype "passive"))
    )
    (net (code "259") (name "Net-(U$30-B)") (class "Default")
      (node (ref "R67") (pin "2") (pinfunction "2_2") (pintype "passive"))
      (node (ref "U$30") (pin "P$1") (pinfunction "B_P$1") (pintype "passive"))
    )
    (net (code "260") (name "Net-(U$30-C)") (class "Default")
      (node (ref "R104") (pin "1") (pinfunction "1_1") (pintype "passive"))
      (node (ref "U$30") (pin "P$3") (pinfunction "C_P$3") (pintype "passive"))
    )
    (net (code "261") (name "Net-(U$31-B)") (class "Default")
      (node (ref "R68") (pin "2") (pinfunction "2_2") (pintype "passive"))
      (node (ref "U$31") (pin "P$1") (pinfunction "B_P$1") (pintype "passive"))
    )
    (net (code "262") (name "Net-(U$31-C)") (class "Default")
      (node (ref "R139") (pin "2") (pinfunction "2_2") (pintype "passive"))
      (node (ref "U$31") (pin "P$3") (pinfunction "C_P$3") (pintype "passive"))
    )
    (net (code "263") (name "Net-(U$32-B)") (class "Default")
      (node (ref "R69") (pin "2") (pinfunction "2_2") (pintype "passive"))
      (node (ref "U$32") (pin "P$1") (pinfunction "B_P$1") (pintype "passive"))
    )
    (net (code "264") (name "Net-(U$32-C)") (class "Default")
      (node (ref "R106") (pin "1") (pinfunction "1_1") (pintype "passive"))
      (node (ref "U$32") (pin "P$3") (pinfunction "C_P$3") (pintype "passive"))
    )
    (net (code "265") (name "Net-(U$33-B)") (class "Default")
      (node (ref "R70") (pin "2") (pinfunction "2_2") (pintype "passive"))
      (node (ref "U$33") (pin "P$1") (pinfunction "B_P$1") (pintype "passive"))
    )
    (net (code "266") (name "Net-(U$33-C)") (class "Default")
      (node (ref "R140") (pin "2") (pinfunction "2_2") (pintype "passive"))
      (node (ref "U$33") (pin "P$3") (pinfunction "C_P$3") (pintype "passive"))
    )
    (net (code "267") (name "Net-(U$34-B)") (class "Default")
      (node (ref "R71") (pin "2") (pinfunction "2_2") (pintype "passive"))
      (node (ref "U$34") (pin "P$1") (pinfunction "B_P$1") (pintype "passive"))
    )
    (net (code "268") (name "Net-(U$34-C)") (class "Default")
      (node (ref "R111") (pin "1") (pinfunction "1_1") (pintype "passive"))
      (node (ref "U$34") (pin "P$3") (pinfunction "C_P$3") (pintype "passive"))
    )
    (net (code "269") (name "Net-(U$35-B)") (class "Default")
      (node (ref "R72") (pin "2") (pinfunction "2_2") (pintype "passive"))
      (node (ref "U$35") (pin "P$1") (pinfunction "B_P$1") (pintype "passive"))
    )
    (net (code "270") (name "Net-(U$35-C)") (class "Default")
      (node (ref "R142") (pin "2") (pinfunction "2_2") (pintype "passive"))
      (node (ref "U$35") (pin "P$3") (pinfunction "C_P$3") (pintype "passive"))
    )
    (net (code "271") (name "Net-(U$36-B)") (class "Default")
      (node (ref "R73") (pin "2") (pinfunction "2_2") (pintype "passive"))
      (node (ref "U$36") (pin "P$1") (pinfunction "B_P$1") (pintype "passive"))
    )
    (net (code "272") (name "Net-(U$36-C)") (class "Default")
      (node (ref "R113") (pin "1") (pinfunction "1_1") (pintype "passive"))
      (node (ref "U$36") (pin "P$3") (pinfunction "C_P$3") (pintype "passive"))
    )
    (net (code "273") (name "Net-(U$37-B)") (class "Default")
      (node (ref "R74") (pin "2") (pinfunction "2_2") (pintype "passive"))
      (node (ref "U$37") (pin "P$1") (pinfunction "B_P$1") (pintype "passive"))
    )
    (net (code "274") (name "Net-(U$37-C)") (class "Default")
      (node (ref "R141") (pin "2") (pinfunction "2_2") (pintype "passive"))
      (node (ref "U$37") (pin "P$3") (pinfunction "C_P$3") (pintype "passive"))
    )
    (net (code "275") (name "Net-(U$38-B)") (class "Default")
      (node (ref "R75") (pin "2") (pinfunction "2_2") (pintype "passive"))
      (node (ref "U$38") (pin "P$1") (pinfunction "B_P$1") (pintype "passive"))
    )
    (net (code "276") (name "Net-(U$38-C)") (class "Default")
      (node (ref "R112") (pin "1") (pinfunction "1_1") (pintype "passive"))
      (node (ref "U$38") (pin "P$3") (pinfunction "C_P$3") (pintype "passive"))
    )
    (net (code "277") (name "Net-(U$39-B)") (class "Default")
      (node (ref "R76") (pin "2") (pinfunction "2_2") (pintype "passive"))
      (node (ref "U$39") (pin "P$1") (pinfunction "B_P$1") (pintype "passive"))
    )
    (net (code "278") (name "Net-(U$39-C)") (class "Default")
      (node (ref "R143") (pin "2") (pinfunction "2_2") (pintype "passive"))
      (node (ref "U$39") (pin "P$3") (pinfunction "C_P$3") (pintype "passive"))
    )
    (net (code "279") (name "Net-(U$40-B)") (class "Default")
      (node (ref "R77") (pin "2") (pinfunction "2_2") (pintype "passive"))
      (node (ref "U$40") (pin "P$1") (pinfunction "B_P$1") (pintype "passive"))
    )
    (net (code "280") (name "Net-(U$40-C)") (class "Default")
      (node (ref "R114") (pin "1") (pinfunction "1_1") (pintype "passive"))
      (node (ref "U$40") (pin "P$3") (pinfunction "C_P$3") (pintype "passive"))
    )
    (net (code "281") (name "Net-(U$41-B)") (class "Default")
      (node (ref "R78") (pin "2") (pinfunction "2_2") (pintype "passive"))
      (node (ref "U$41") (pin "P$1") (pinfunction "B_P$1") (pintype "passive"))
    )
    (net (code "282") (name "Net-(U$41-C)") (class "Default")
      (node (ref "R144") (pin "2") (pinfunction "2_2") (pintype "passive"))
      (node (ref "U$41") (pin "P$3") (pinfunction "C_P$3") (pintype "passive"))
    )
    (net (code "283") (name "Net-(U$42-B)") (class "Default")
      (node (ref "R79") (pin "2") (pinfunction "2_2") (pintype "passive"))
      (node (ref "U$42") (pin "P$1") (pinfunction "B_P$1") (pintype "passive"))
    )
    (net (code "284") (name "Net-(U$42-C)") (class "Default")
      (node (ref "R115") (pin "1") (pinfunction "1_1") (pintype "passive"))
      (node (ref "U$42") (pin "P$3") (pinfunction "C_P$3") (pintype "passive"))
    )
    (net (code "285") (name "Net-(U$43-B)") (class "Default")
      (node (ref "R80") (pin "2") (pinfunction "2_2") (pintype "passive"))
      (node (ref "U$43") (pin "P$1") (pinfunction "B_P$1") (pintype "passive"))
    )
    (net (code "286") (name "Net-(U$43-C)") (class "Default")
      (node (ref "R146") (pin "2") (pinfunction "2_2") (pintype "passive"))
      (node (ref "U$43") (pin "P$3") (pinfunction "C_P$3") (pintype "passive"))
    )
    (net (code "287") (name "Net-(U$44-B)") (class "Default")
      (node (ref "R81") (pin "2") (pinfunction "2_2") (pintype "passive"))
      (node (ref "U$44") (pin "P$1") (pinfunction "B_P$1") (pintype "passive"))
    )
    (net (code "288") (name "Net-(U$44-C)") (class "Default")
      (node (ref "R117") (pin "1") (pinfunction "1_1") (pintype "passive"))
      (node (ref "U$44") (pin "P$3") (pinfunction "C_P$3") (pintype "passive"))
    )
    (net (code "289") (name "Net-(U$45-B)") (class "Default")
      (node (ref "R82") (pin "2") (pinfunction "2_2") (pintype "passive"))
      (node (ref "U$45") (pin "P$1") (pinfunction "B_P$1") (pintype "passive"))
    )
    (net (code "290") (name "Net-(U$45-C)") (class "Default")
      (node (ref "R145") (pin "2") (pinfunction "2_2") (pintype "passive"))
      (node (ref "U$45") (pin "P$3") (pinfunction "C_P$3") (pintype "passive"))
    )
    (net (code "291") (name "Net-(U$46-B)") (class "Default")
      (node (ref "R83") (pin "2") (pinfunction "2_2") (pintype "passive"))
      (node (ref "U$46") (pin "P$1") (pinfunction "B_P$1") (pintype "passive"))
    )
    (net (code "292") (name "Net-(U$46-C)") (class "Default")
      (node (ref "R116") (pin "1") (pinfunction "1_1") (pintype "passive"))
      (node (ref "U$46") (pin "P$3") (pinfunction "C_P$3") (pintype "passive"))
    )
    (net (code "293") (name "Net-(U$47-B)") (class "Default")
      (node (ref "R84") (pin "2") (pinfunction "2_2") (pintype "passive"))
      (node (ref "U$47") (pin "P$1") (pinfunction "B_P$1") (pintype "passive"))
    )
    (net (code "294") (name "Net-(U$47-C)") (class "Default")
      (node (ref "R147") (pin "2") (pinfunction "2_2") (pintype "passive"))
      (node (ref "U$47") (pin "P$3") (pinfunction "C_P$3") (pintype "passive"))
    )
    (net (code "295") (name "Net-(U$48-B)") (class "Default")
      (node (ref "R85") (pin "2") (pinfunction "2_2") (pintype "passive"))
      (node (ref "U$48") (pin "P$1") (pinfunction "B_P$1") (pintype "passive"))
    )
    (net (code "296") (name "Net-(U$48-C)") (class "Default")
      (node (ref "R118") (pin "1") (pinfunction "1_1") (pintype "passive"))
      (node (ref "U$48") (pin "P$3") (pinfunction "C_P$3") (pintype "passive"))
    )
    (net (code "297") (name "Net-(U$49-B)") (class "Default")
      (node (ref "R86") (pin "2") (pinfunction "2_2") (pintype "passive"))
      (node (ref "U$49") (pin "P$1") (pinfunction "B_P$1") (pintype "passive"))
    )
    (net (code "298") (name "Net-(U$49-C)") (class "Default")
      (node (ref "R148") (pin "2") (pinfunction "2_2") (pintype "passive"))
      (node (ref "U$49") (pin "P$3") (pinfunction "C_P$3") (pintype "passive"))
    )
    (net (code "299") (name "Net-(U$50-B)") (class "Default")
      (node (ref "R87") (pin "2") (pinfunction "2_2") (pintype "passive"))
      (node (ref "U$50") (pin "P$1") (pinfunction "B_P$1") (pintype "passive"))
    )
    (net (code "300") (name "Net-(U$50-C)") (class "Default")
      (node (ref "R119") (pin "1") (pinfunction "1_1") (pintype "passive"))
      (node (ref "U$50") (pin "P$3") (pinfunction "C_P$3") (pintype "passive"))
    )
    (net (code "301") (name "Net-(U$51-B)") (class "Default")
      (node (ref "R88") (pin "2") (pinfunction "2_2") (pintype "passive"))
      (node (ref "U$51") (pin "P$1") (pinfunction "B_P$1") (pintype "passive"))
    )
    (net (code "302") (name "Net-(U$51-C)") (class "Default")
      (node (ref "R150") (pin "2") (pinfunction "2_2") (pintype "passive"))
      (node (ref "U$51") (pin "P$3") (pinfunction "C_P$3") (pintype "passive"))
    )
    (net (code "303") (name "Net-(U$52-B)") (class "Default")
      (node (ref "R89") (pin "2") (pinfunction "2_2") (pintype "passive"))
      (node (ref "U$52") (pin "P$1") (pinfunction "B_P$1") (pintype "passive"))
    )
    (net (code "304") (name "Net-(U$52-C)") (class "Default")
      (node (ref "R122") (pin "1") (pinfunction "1_1") (pintype "passive"))
      (node (ref "U$52") (pin "P$3") (pinfunction "C_P$3") (pintype "passive"))
    )
    (net (code "305") (name "Net-(U$53-B)") (class "Default")
      (node (ref "R90") (pin "2") (pinfunction "2_2") (pintype "passive"))
      (node (ref "U$53") (pin "P$1") (pinfunction "B_P$1") (pintype "passive"))
    )
    (net (code "306") (name "Net-(U$53-C)") (class "Default")
      (node (ref "R149") (pin "2") (pinfunction "2_2") (pintype "passive"))
      (node (ref "U$53") (pin "P$3") (pinfunction "C_P$3") (pintype "passive"))
    )
    (net (code "307") (name "Net-(U$54-B)") (class "Default")
      (node (ref "R91") (pin "2") (pinfunction "2_2") (pintype "passive"))
      (node (ref "U$54") (pin "P$1") (pinfunction "B_P$1") (pintype "passive"))
    )
    (net (code "308") (name "Net-(U$54-C)") (class "Default")
      (node (ref "R120") (pin "1") (pinfunction "1_1") (pintype "passive"))
      (node (ref "U$54") (pin "P$3") (pinfunction "C_P$3") (pintype "passive"))
    )
    (net (code "309") (name "Net-(U$55-B)") (class "Default")
      (node (ref "R92") (pin "2") (pinfunction "2_2") (pintype "passive"))
      (node (ref "U$55") (pin "P$1") (pinfunction "B_P$1") (pintype "passive"))
    )
    (net (code "310") (name "Net-(U$55-C)") (class "Default")
      (node (ref "R151") (pin "2") (pinfunction "2_2") (pintype "passive"))
      (node (ref "U$55") (pin "P$3") (pinfunction "C_P$3") (pintype "passive"))
    )
    (net (code "311") (name "Net-(U$56-B)") (class "Default")
      (node (ref "R93") (pin "2") (pinfunction "2_2") (pintype "passive"))
      (node (ref "U$56") (pin "P$1") (pinfunction "B_P$1") (pintype "passive"))
    )
    (net (code "312") (name "Net-(U$56-C)") (class "Default")
      (node (ref "R121") (pin "1") (pinfunction "1_1") (pintype "passive"))
      (node (ref "U$56") (pin "P$3") (pinfunction "C_P$3") (pintype "passive"))
    )
    (net (code "313") (name "Net-(U$57-B)") (class "Default")
      (node (ref "R94") (pin "2") (pinfunction "2_2") (pintype "passive"))
      (node (ref "U$57") (pin "P$1") (pinfunction "B_P$1") (pintype "passive"))
    )
    (net (code "314") (name "Net-(U$57-C)") (class "Default")
      (node (ref "R152") (pin "2") (pinfunction "2_2") (pintype "passive"))
      (node (ref "U$57") (pin "P$3") (pinfunction "C_P$3") (pintype "passive"))
    )
    (net (code "315") (name "Net-(U$58-B)") (class "Default")
      (node (ref "R95") (pin "2") (pinfunction "2_2") (pintype "passive"))
      (node (ref "U$58") (pin "P$1") (pinfunction "B_P$1") (pintype "passive"))
    )
    (net (code "316") (name "Net-(U$58-C)") (class "Default")
      (node (ref "R123") (pin "1") (pinfunction "1_1") (pintype "passive"))
      (node (ref "U$58") (pin "P$3") (pinfunction "C_P$3") (pintype "passive"))
    )
    (net (code "317") (name "Net-(U$59-B)") (class "Default")
      (node (ref "R96") (pin "2") (pinfunction "2_2") (pintype "passive"))
      (node (ref "U$59") (pin "P$1") (pinfunction "B_P$1") (pintype "passive"))
    )
    (net (code "318") (name "Net-(U$59-C)") (class "Default")
      (node (ref "R156") (pin "2") (pinfunction "2_2") (pintype "passive"))
      (node (ref "U$59") (pin "P$3") (pinfunction "C_P$3") (pintype "passive"))
    )
    (net (code "319") (name "Net-(U$60-B)") (class "Default")
      (node (ref "R97") (pin "2") (pinfunction "2_2") (pintype "passive"))
      (node (ref "U$60") (pin "P$1") (pinfunction "B_P$1") (pintype "passive"))
    )
    (net (code "320") (name "Net-(U$60-C)") (class "Default")
      (node (ref "R125") (pin "1") (pinfunction "1_1") (pintype "passive"))
      (node (ref "U$60") (pin "P$3") (pinfunction "C_P$3") (pintype "passive"))
    )
    (net (code "321") (name "Net-(U$61-B)") (class "Default")
      (node (ref "R98") (pin "2") (pinfunction "2_2") (pintype "passive"))
      (node (ref "U$61") (pin "P$1") (pinfunction "B_P$1") (pintype "passive"))
    )
    (net (code "322") (name "Net-(U$61-C)") (class "Default")
      (node (ref "R153") (pin "2") (pinfunction "2_2") (pintype "passive"))
      (node (ref "U$61") (pin "P$3") (pinfunction "C_P$3") (pintype "passive"))
    )
    (net (code "323") (name "Net-(U$62-B)") (class "Default")
      (node (ref "R99") (pin "2") (pinfunction "2_2") (pintype "passive"))
      (node (ref "U$62") (pin "P$1") (pinfunction "B_P$1") (pintype "passive"))
    )
    (net (code "324") (name "Net-(U$62-C)") (class "Default")
      (node (ref "R124") (pin "1") (pinfunction "1_1") (pintype "passive"))
      (node (ref "U$62") (pin "P$3") (pinfunction "C_P$3") (pintype "passive"))
    )
    (net (code "325") (name "Net-(U$63-B)") (class "Default")
      (node (ref "R100") (pin "2") (pinfunction "2_2") (pintype "passive"))
      (node (ref "U$63") (pin "P$1") (pinfunction "B_P$1") (pintype "passive"))
    )
    (net (code "326") (name "Net-(U$63-C)") (class "Default")
      (node (ref "R157") (pin "2") (pinfunction "2_2") (pintype "passive"))
      (node (ref "U$63") (pin "P$3") (pinfunction "C_P$3") (pintype "passive"))
    )
    (net (code "327") (name "Net-(U$64-B)") (class "Default")
      (node (ref "R101") (pin "2") (pinfunction "2_2") (pintype "passive"))
      (node (ref "U$64") (pin "P$1") (pinfunction "B_P$1") (pintype "passive"))
    )
    (net (code "328") (name "Net-(U$64-C)") (class "Default")
      (node (ref "R126") (pin "1") (pinfunction "1_1") (pintype "passive"))
      (node (ref "U$64") (pin "P$3") (pinfunction "C_P$3") (pintype "passive"))
    )
    (net (code "329") (name "Net-(U$65-B)") (class "Default")
      (node (ref "R102") (pin "2") (pinfunction "2_2") (pintype "passive"))
      (node (ref "U$65") (pin "P$1") (pinfunction "B_P$1") (pintype "passive"))
    )
    (net (code "330") (name "Net-(U$65-C)") (class "Default")
      (node (ref "R158") (pin "2") (pinfunction "2_2") (pintype "passive"))
      (node (ref "U$65") (pin "P$3") (pinfunction "C_P$3") (pintype "passive"))
    )
    (net (code "331") (name "Net-(U$66-G)") (class "Default")
      (node (ref "R2") (pin "2") (pinfunction "2_2") (pintype "passive"))
      (node (ref "R23") (pin "1") (pinfunction "1_1") (pintype "passive"))
      (node (ref "U$66") (pin "1") (pinfunction "G_1") (pintype "passive"))
    )
    (net (code "332") (name "Net-(U$67-G)") (class "Default")
      (node (ref "R24") (pin "1") (pinfunction "1_1") (pintype "passive"))
      (node (ref "R3") (pin "2") (pinfunction "2_2") (pintype "passive"))
      (node (ref "U$67") (pin "1") (pinfunction "G_1") (pintype "passive"))
    )
    (net (code "333") (name "Net-(U$68-G)") (class "Default")
      (node (ref "R25") (pin "1") (pinfunction "1_1") (pintype "passive"))
      (node (ref "R4") (pin "2") (pinfunction "2_2") (pintype "passive"))
      (node (ref "U$68") (pin "1") (pinfunction "G_1") (pintype "passive"))
    )
    (net (code "334") (name "Net-(U$69-G)") (class "Default")
      (node (ref "R26") (pin "1") (pinfunction "1_1") (pintype "passive"))
      (node (ref "R5") (pin "2") (pinfunction "2_2") (pintype "passive"))
      (node (ref "U$69") (pin "1") (pinfunction "G_1") (pintype "passive"))
    )
    (net (code "335") (name "Net-(U$70-G)") (class "Default")
      (node (ref "R27") (pin "1") (pinfunction "1_1") (pintype "passive"))
      (node (ref "R6") (pin "2") (pinfunction "2_2") (pintype "passive"))
      (node (ref "U$70") (pin "1") (pinfunction "G_1") (pintype "passive"))
    )
    (net (code "336") (name "Net-(U$71-G)") (class "Default")
      (node (ref "R28") (pin "1") (pinfunction "1_1") (pintype "passive"))
      (node (ref "R7") (pin "2") (pinfunction "2_2") (pintype "passive"))
      (node (ref "U$71") (pin "1") (pinfunction "G_1") (pintype "passive"))
    )
    (net (code "337") (name "Net-(U$72-G)") (class "Default")
      (node (ref "R29") (pin "1") (pinfunction "1_1") (pintype "passive"))
      (node (ref "R8") (pin "2") (pinfunction "2_2") (pintype "passive"))
      (node (ref "U$72") (pin "1") (pinfunction "G_1") (pintype "passive"))
    )
    (net (code "338") (name "Net-(U$73-G)") (class "Default")
      (node (ref "R30") (pin "1") (pinfunction "1_1") (pintype "passive"))
      (node (ref "R9") (pin "2") (pinfunction "2_2") (pintype "passive"))
      (node (ref "U$73") (pin "1") (pinfunction "G_1") (pintype "passive"))
    )
    (net (code "339") (name "VCC") (class "Default")
      (node (ref "C1") (pin "2") (pinfunction "2_2") (pintype "passive"))
      (node (ref "C10") (pin "2") (pinfunction "2_2") (pintype "passive"))
      (node (ref "C16") (pin "1") (pinfunction "1_1") (pintype "passive"))
      (node (ref "C17") (pin "1") (pinfunction "1_1") (pintype "passive"))
      (node (ref "C22") (pin "2") (pinfunction "2_2") (pintype "passive"))
      (node (ref "C23") (pin "2") (pinfunction "2_2") (pintype "passive"))
      (node (ref "C24") (pin "2") (pinfunction "2_2") (pintype "passive"))
      (node (ref "C25") (pin "2") (pinfunction "2_2") (pintype "passive"))
      (node (ref "C26") (pin "2") (pinfunction "2_2") (pintype "passive"))
      (node (ref "C27") (pin "2") (pinfunction "2_2") (pintype "passive"))
      (node (ref "C28") (pin "2") (pinfunction "2_2") (pintype "passive"))
      (node (ref "C29") (pin "2") (pinfunction "2_2") (pintype "passive"))
      (node (ref "C3") (pin "1") (pinfunction "1_1") (pintype "passive"))
      (node (ref "C30") (pin "2") (pinfunction "2_2") (pintype "passive"))
      (node (ref "C7") (pin "2") (pinfunction "2_2") (pintype "passive"))
      (node (ref "C8") (pin "2") (pinfunction "2_2") (pintype "passive"))
      (node (ref "C9") (pin "2") (pinfunction "2_2") (pintype "passive"))
      (node (ref "IC1") (pin "18") (pinfunction "AVCC_18") (pintype "power_in"))
      (node (ref "IC1") (pin "4") (pinfunction "VCC_4") (pintype "power_in"))
      (node (ref "IC1") (pin "6") (pinfunction "VCC_6") (pintype "power_in"))
      (node (ref "IC10") (pin "20") (pinfunction "VCC_20") (pintype "power_in"))
      (node (ref "IC10") (pin "4") (pinfunction "VCCIO_4") (pintype "power_in"))
      (node (ref "IC11") (pin "PH") (pinfunction "VCC_PH") (pintype "power_in"))
      (node (ref "IC12") (pin "1") (pinfunction "VDDA_1") (pintype "power_in"))
      (node (ref "IC14") (pin "17") (pinfunction "VCC1_17") (pintype "power_in"))
      (node (ref "IC14") (pin "27") (pinfunction "AVCC_27") (pintype "power_in"))
      (node (ref "IC14") (pin "38") (pinfunction "VCC2_38") (pintype "power_in"))
      (node (ref "IC14") (pin "5") (pinfunction "VCC_5") (pintype "power_in"))
      (node (ref "JP1") (pin "10") (pinfunction "VCC_10") (pintype "power_in"))
      (node (ref "JP2") (pin "2") (pinfunction "2_2") (pintype "passive"))
      (node (ref "JP3") (pin "2") (pinfunction "+5V_2") (pintype "power_in"))
      (node (ref "JP6") (pin "2") (pinfunction "+5V_2") (pintype "power_in"))
      (node (ref "R1") (pin "1") (pinfunction "1_1") (pintype "passive"))
      (node (ref "R12") (pin "2") (pinfunction "2_2") (pintype "passive"))
      (node (ref "R13") (pin "2") (pinfunction "2_2") (pintype "passive"))
      (node (ref "R15") (pin "1") (pinfunction "1_1") (pintype "passive"))
      (node (ref "R18") (pin "A") (pinfunction "A_A") (pintype "passive"))
      (node (ref "R19") (pin "2") (pinfunction "2_2") (pintype "passive"))
      (node (ref "R20") (pin "1") (pinfunction "1_1") (pintype "passive"))
      (node (ref "U$10") (pin "P$2") (pinfunction "E_P$2") (pintype "passive"))
      (node (ref "U$11") (pin "P$2") (pinfunction "E_P$2") (pintype "passive"))
      (node (ref "U$12") (pin "P$2") (pinfunction "E_P$2") (pintype "passive"))
      (node (ref "U$13") (pin "P$2") (pinfunction "E_P$2") (pintype "passive"))
      (node (ref "U$14") (pin "P$2") (pinfunction "E_P$2") (pintype "passive"))
      (node (ref "U$15") (pin "P$2") (pinfunction "E_P$2") (pintype "passive"))
      (node (ref "U$16") (pin "P$2") (pinfunction "E_P$2") (pintype "passive"))
      (node (ref "U$17") (pin "P$2") (pinfunction "E_P$2") (pintype "passive"))
      (node (ref "U$18") (pin "P$2") (pinfunction "E_P$2") (pintype "passive"))
      (node (ref "U$19") (pin "P$2") (pinfunction "E_P$2") (pintype "passive"))
      (node (ref "U$2") (pin "P$2") (pinfunction "E_P$2") (pintype "passive"))
      (node (ref "U$20") (pin "P$2") (pinfunction "E_P$2") (pintype "passive"))
      (node (ref "U$21") (pin "P$2") (pinfunction "E_P$2") (pintype "passive"))
      (node (ref "U$22") (pin "P$2") (pinfunction "E_P$2") (pintype "passive"))
      (node (ref "U$23") (pin "P$2") (pinfunction "E_P$2") (pintype "passive"))
      (node (ref "U$24") (pin "P$2") (pinfunction "E_P$2") (pintype "passive"))
      (node (ref "U$25") (pin "P$2") (pinfunction "E_P$2") (pintype "passive"))
      (node (ref "U$26") (pin "P$2") (pinfunction "E_P$2") (pintype "passive"))
      (node (ref "U$27") (pin "P$2") (pinfunction "E_P$2") (pintype "passive"))
      (node (ref "U$28") (pin "P$2") (pinfunction "E_P$2") (pintype "passive"))
      (node (ref "U$29") (pin "P$2") (pinfunction "E_P$2") (pintype "passive"))
      (node (ref "U$3") (pin "P$2") (pinfunction "E_P$2") (pintype "passive"))
      (node (ref "U$30") (pin "P$2") (pinfunction "E_P$2") (pintype "passive"))
      (node (ref "U$31") (pin "P$2") (pinfunction "E_P$2") (pintype "passive"))
      (node (ref "U$32") (pin "P$2") (pinfunction "E_P$2") (pintype "passive"))
      (node (ref "U$33") (pin "P$2") (pinfunction "E_P$2") (pintype "passive"))
      (node (ref "U$34") (pin "P$2") (pinfunction "E_P$2") (pintype "passive"))
      (node (ref "U$35") (pin "P$2") (pinfunction "E_P$2") (pintype "passive"))
      (node (ref "U$36") (pin "P$2") (pinfunction "E_P$2") (pintype "passive"))
      (node (ref "U$37") (pin "P$2") (pinfunction "E_P$2") (pintype "passive"))
      (node (ref "U$38") (pin "P$2") (pinfunction "E_P$2") (pintype "passive"))
      (node (ref "U$39") (pin "P$2") (pinfunction "E_P$2") (pintype "passive"))
      (node (ref "U$4") (pin "P$2") (pinfunction "E_P$2") (pintype "passive"))
      (node (ref "U$40") (pin "P$2") (pinfunction "E_P$2") (pintype "passive"))
      (node (ref "U$41") (pin "P$2") (pinfunction "E_P$2") (pintype "passive"))
      (node (ref "U$42") (pin "P$2") (pinfunction "E_P$2") (pintype "passive"))
      (node (ref "U$43") (pin "P$2") (pinfunction "E_P$2") (pintype "passive"))
      (node (ref "U$44") (pin "P$2") (pinfunction "E_P$2") (pintype "passive"))
      (node (ref "U$45") (pin "P$2") (pinfunction "E_P$2") (pintype "passive"))
      (node (ref "U$46") (pin "P$2") (pinfunction "E_P$2") (pintype "passive"))
      (node (ref "U$47") (pin "P$2") (pinfunction "E_P$2") (pintype "passive"))
      (node (ref "U$48") (pin "P$2") (pinfunction "E_P$2") (pintype "passive"))
      (node (ref "U$49") (pin "P$2") (pinfunction "E_P$2") (pintype "passive"))
      (node (ref "U$5") (pin "P$2") (pinfunction "E_P$2") (pintype "passive"))
      (node (ref "U$50") (pin "P$2") (pinfunction "E_P$2") (pintype "passive"))
      (node (ref "U$51") (pin "P$2") (pinfunction "E_P$2") (pintype "passive"))
      (node (ref "U$52") (pin "P$2") (pinfunction "E_P$2") (pintype "passive"))
      (node (ref "U$53") (pin "P$2") (pinfunction "E_P$2") (pintype "passive"))
      (node (ref "U$54") (pin "P$2") (pinfunction "E_P$2") (pintype "passive"))
      (node (ref "U$55") (pin "P$2") (pinfunction "E_P$2") (pintype "passive"))
      (node (ref "U$56") (pin "P$2") (pinfunction "E_P$2") (pintype "passive"))
      (node (ref "U$57") (pin "P$2") (pinfunction "E_P$2") (pintype "passive"))
      (node (ref "U$58") (pin "P$2") (pinfunction "E_P$2") (pintype "passive"))
      (node (ref "U$59") (pin "P$2") (pinfunction "E_P$2") (pintype "passive"))
      (node (ref "U$6") (pin "P$2") (pinfunction "E_P$2") (pintype "passive"))
      (node (ref "U$60") (pin "P$2") (pinfunction "E_P$2") (pintype "passive"))
      (node (ref "U$61") (pin "P$2") (pinfunction "E_P$2") (pintype "passive"))
      (node (ref "U$62") (pin "P$2") (pinfunction "E_P$2") (pintype "passive"))
      (node (ref "U$63") (pin "P$2") (pinfunction "E_P$2") (pintype "passive"))
      (node (ref "U$64") (pin "P$2") (pinfunction "E_P$2") (pintype "passive"))
      (node (ref "U$65") (pin "P$2") (pinfunction "E_P$2") (pintype "passive"))
      (node (ref "U$7") (pin "P$2") (pinfunction "E_P$2") (pintype "passive"))
      (node (ref "U$8") (pin "P$2") (pinfunction "E_P$2") (pintype "passive"))
      (node (ref "U$9") (pin "P$2") (pinfunction "E_P$2") (pintype "passive"))
    )
    (net (code "340") (name "unconnected-(IC1-ADC6-Pad19)") (class "Default")
      (node (ref "IC1") (pin "19") (pinfunction "ADC6_19") (pintype "bidirectional"))
    )
    (net (code "341") (name "unconnected-(IC1-ADC7-Pad22)") (class "Default")
      (node (ref "IC1") (pin "22") (pinfunction "ADC7_22") (pintype "bidirectional"))
    )
    (net (code "342") (name "unconnected-(IC1-PB0(ICP)-Pad12)") (class "Default")
      (node (ref "IC1") (pin "12") (pinfunction "PB0(ICP)_12") (pintype "bidirectional"))
    )
    (net (code "343") (name "unconnected-(IC1-PD0(RXD)-Pad30)") (class "Default")
      (node (ref "IC1") (pin "30") (pinfunction "PD0(RXD)_30") (pintype "bidirectional"))
    )
    (net (code "344") (name "unconnected-(IC1-PD1(TXD)-Pad31)") (class "Default")
      (node (ref "IC1") (pin "31") (pinfunction "PD1(TXD)_31") (pintype "bidirectional"))
    )
    (net (code "345") (name "unconnected-(IC1-PD2(INT0)-Pad32)") (class "Default")
      (node (ref "IC1") (pin "32") (pinfunction "PD2(INT0)_32") (pintype "bidirectional"))
    )
    (net (code "346") (name "unconnected-(IC1-PD3(INT1)-Pad1)") (class "Default")
      (node (ref "IC1") (pin "1") (pinfunction "PD3(INT1)_1") (pintype "bidirectional"))
    )
    (net (code "347") (name "unconnected-(IC1-PD4(XCK{slash}T0)-Pad2)") (class "Default")
      (node (ref "IC1") (pin "2") (pinfunction "PD4(XCK/T0)_2") (pintype "bidirectional"))
    )
    (net (code "348") (name "unconnected-(IC1-PD5(T1)-Pad9)") (class "Default")
      (node (ref "IC1") (pin "9") (pinfunction "PD5(T1)_9") (pintype "bidirectional"))
    )
    (net (code "349") (name "unconnected-(IC1-PD6(AIN0)-Pad10)") (class "Default")
      (node (ref "IC1") (pin "10") (pinfunction "PD6(AIN0)_10") (pintype "bidirectional"))
    )
    (net (code "350") (name "unconnected-(IC1-PD7(AIN1)-Pad11)") (class "Default")
      (node (ref "IC1") (pin "11") (pinfunction "PD7(AIN1)_11") (pintype "bidirectional"))
    )
    (net (code "351") (name "unconnected-(IC10-CBUS0-Pad23)") (class "Default")
      (node (ref "IC10") (pin "23") (pinfunction "CBUS0_23") (pintype "bidirectional"))
    )
    (net (code "352") (name "unconnected-(IC10-CBUS1-Pad22)") (class "Default")
      (node (ref "IC10") (pin "22") (pinfunction "CBUS1_22") (pintype "bidirectional"))
    )
    (net (code "353") (name "unconnected-(IC10-CBUS2-Pad13)") (class "Default")
      (node (ref "IC10") (pin "13") (pinfunction "CBUS2_13") (pintype "bidirectional"))
    )
    (net (code "354") (name "unconnected-(IC10-CBUS3-Pad14)") (class "Default")
      (node (ref "IC10") (pin "14") (pinfunction "CBUS3_14") (pintype "bidirectional"))
    )
    (net (code "355") (name "unconnected-(IC10-CBUS4-Pad12)") (class "Default")
      (node (ref "IC10") (pin "12") (pinfunction "CBUS4_12") (pintype "bidirectional"))
    )
    (net (code "356") (name "unconnected-(IC10-OSCI-Pad27)") (class "Default")
      (node (ref "IC10") (pin "27") (pinfunction "OSCI_27") (pintype "input"))
    )
    (net (code "357") (name "unconnected-(IC10-OSCO-Pad28)") (class "Default")
      (node (ref "IC10") (pin "28") (pinfunction "OSCO_28") (pintype "output"))
    )
    (net (code "358") (name "unconnected-(IC10-~{CTS}-Pad11)") (class "Default")
      (node (ref "IC10") (pin "11") (pinfunction "~{CTS}_11") (pintype "input"))
    )
    (net (code "359") (name "unconnected-(IC10-~{DCD}-Pad10)") (class "Default")
      (node (ref "IC10") (pin "10") (pinfunction "~{DCD}_10") (pintype "input"))
    )
    (net (code "360") (name "unconnected-(IC10-~{DSR}-Pad9)") (class "Default")
      (node (ref "IC10") (pin "9") (pinfunction "~{DSR}_9") (pintype "input"))
    )
    (net (code "361") (name "unconnected-(IC10-~{DTR}-Pad2)") (class "Default")
      (node (ref "IC10") (pin "2") (pinfunction "~{DTR}_2") (pintype "output"))
    )
    (net (code "362") (name "unconnected-(IC10-~{RI}-Pad6)") (class "Default")
      (node (ref "IC10") (pin "6") (pinfunction "~{RI}_6") (pintype "input"))
    )
    (net (code "363") (name "unconnected-(IC10-~{RTS}-Pad3)") (class "Default")
      (node (ref "IC10") (pin "3") (pinfunction "~{RTS}_3") (pintype "output"))
    )
    (net (code "364") (name "unconnected-(JP3-LED-Pad3)") (class "Default")
      (node (ref "JP3") (pin "3") (pinfunction "LED_3") (pintype "output"))
    )
    (net (code "365") (name "unconnected-(JP6-LED-Pad3)") (class "Default")
      (node (ref "JP6") (pin "3") (pinfunction "LED_3") (pintype "output"))
    )
    (net (code "366") (name "unconnected-(U$1-CL-PadCONLEFT)") (class "Default")
      (node (ref "U$1") (pin "CONLEFT") (pinfunction "CL_CONLEFT") (pintype "bidirectional"))
    )
    (net (code "367") (name "unconnected-(U$1-CR-PadCONRIGHT)") (class "Default")
      (node (ref "U$1") (pin "CONRIGHT") (pinfunction "CR_CONRIGHT") (pintype "bidirectional"))
    )
    (net (code "368") (name "unconnected-(X1-Pad3)") (class "Default")
      (node (ref "X1") (pin "3") (pinfunction "3_3") (pintype "passive"))
    )
    (net (code "369") (name "unconnected-(X2-Pad4)") (class "Default")
      (node (ref "X2") (pin "4") (pinfunction "4_4") (pintype "input"))
    )
  )
)
